# WEB_SERVER.net
KiCad netlist of a schematic drawn in Altium Designer
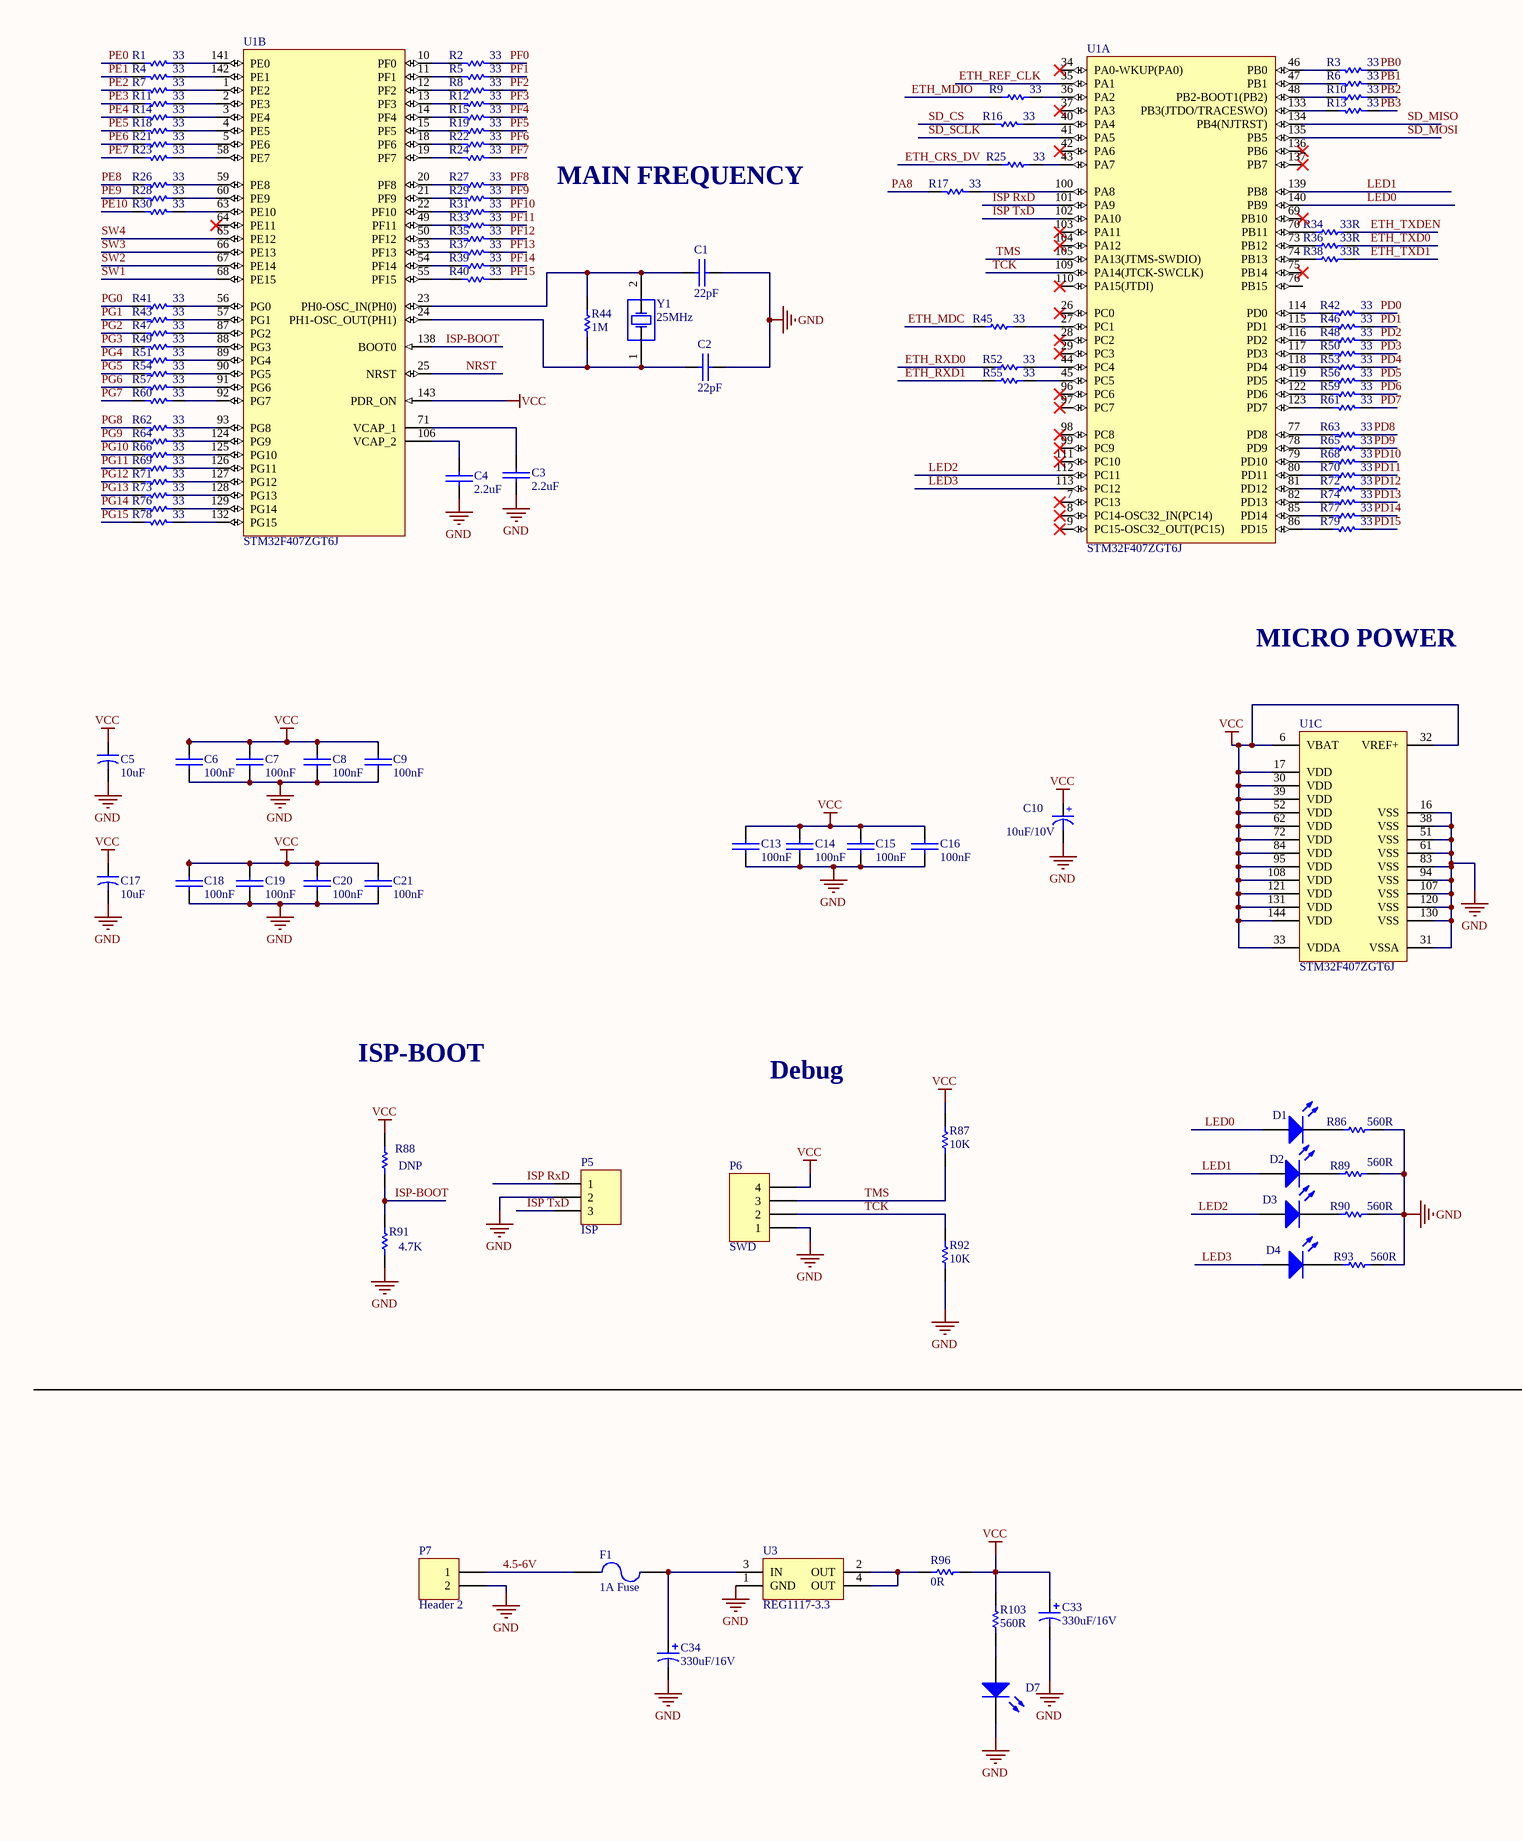
[diagram p0: WEB_SERVER.SchDoc, left]
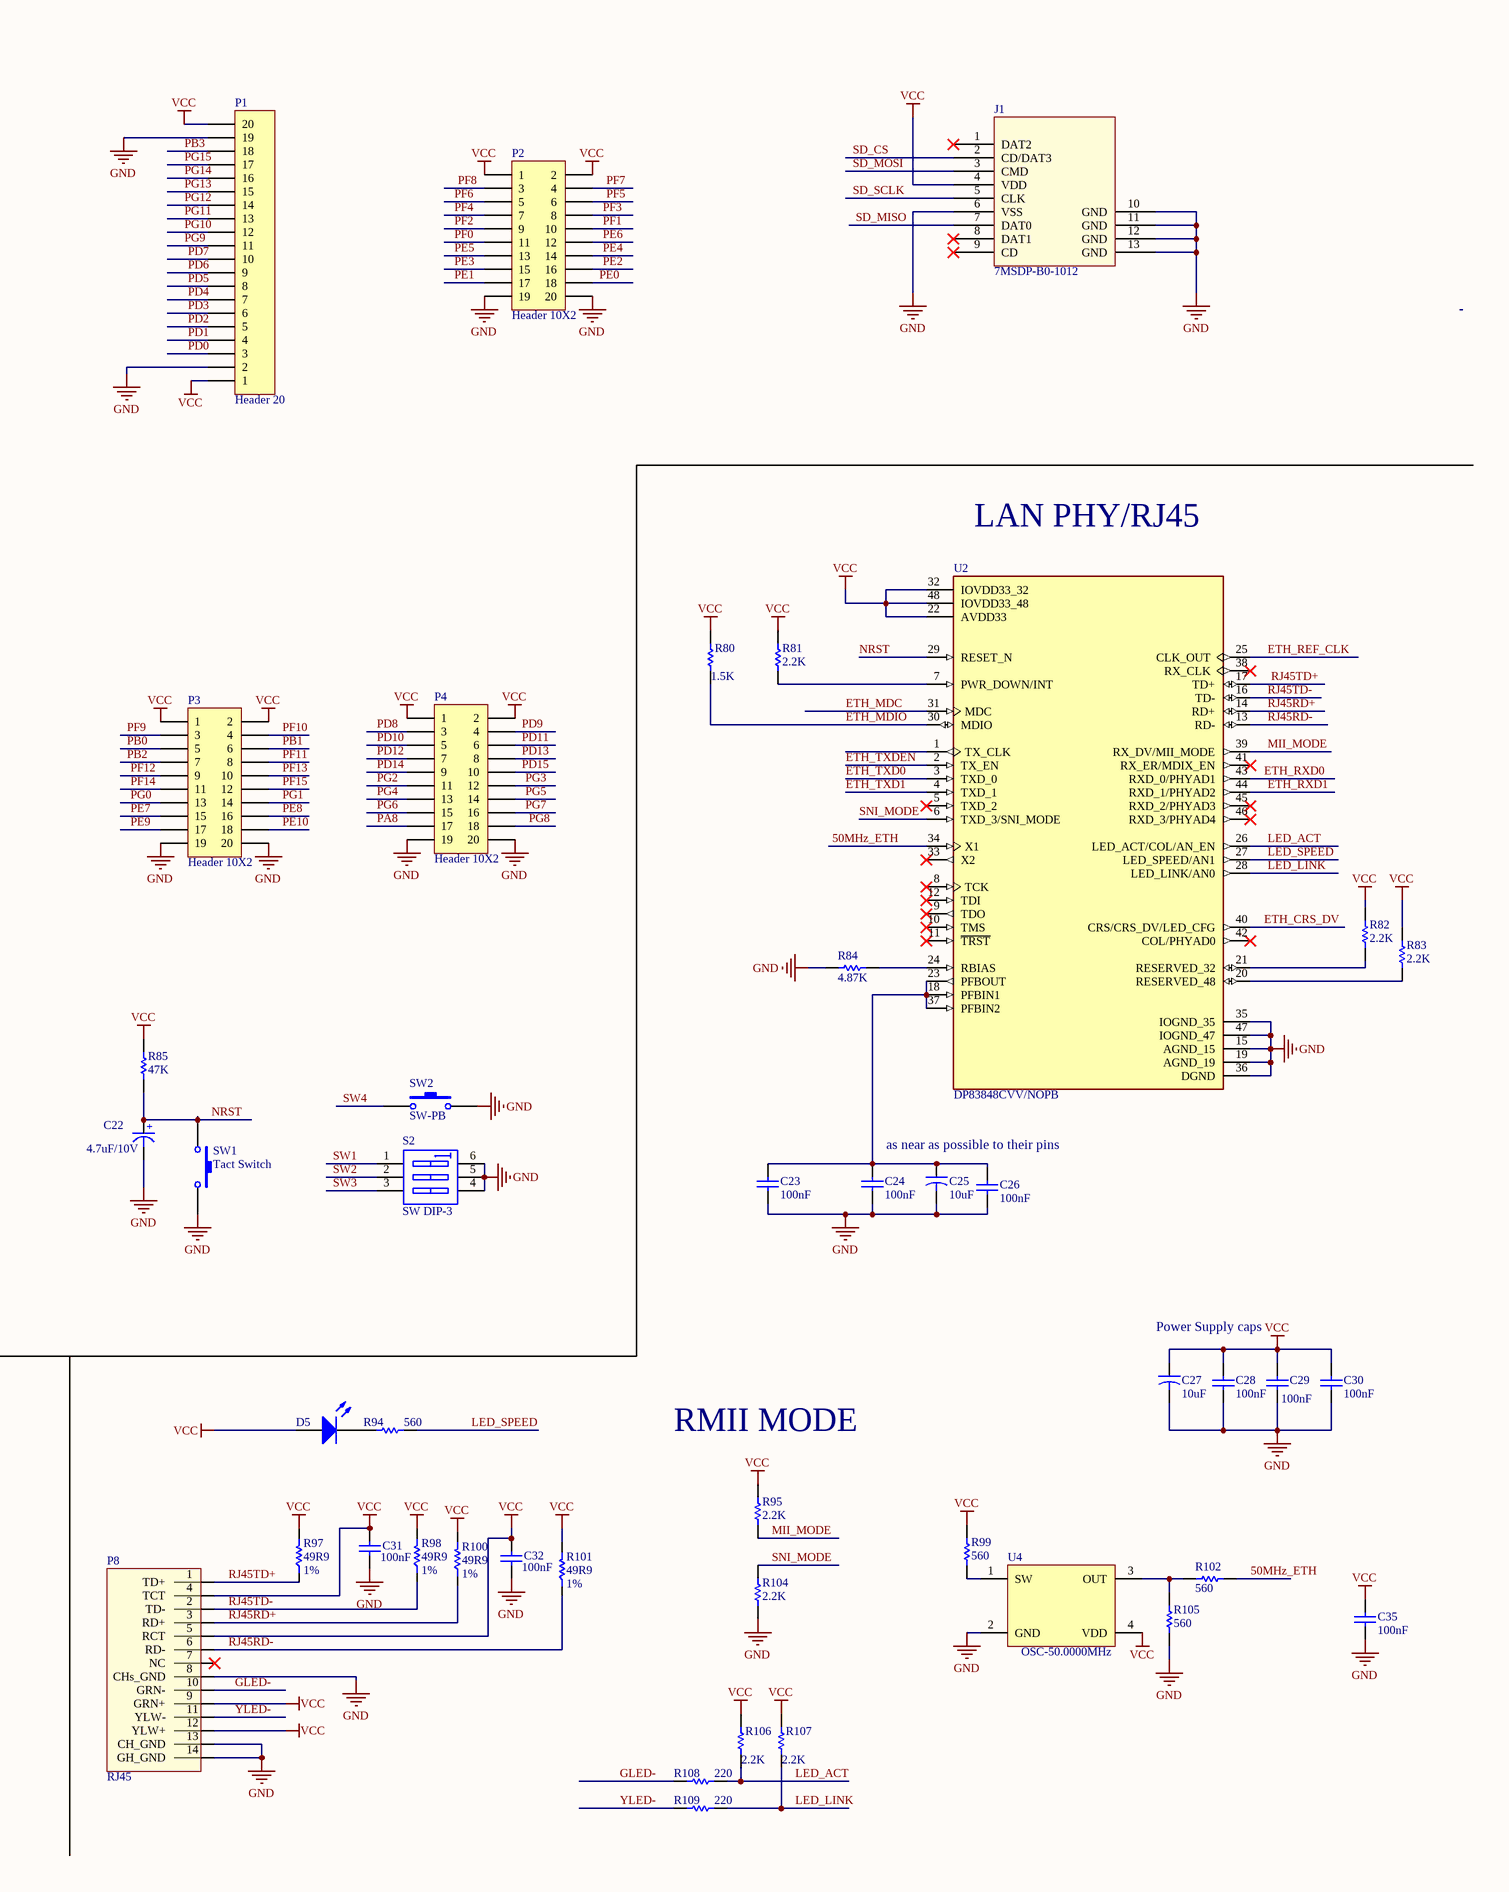
[diagram p1: WEB_SERVER.SchDoc, right]

(export (version "E")
  (design (tool "Eeschema 10.0.6"))
  (components
    (comp (ref "C1")
      (value "22pF")
      (footprint "C0805")
      (description "Bipolar Capacitor")
      (fields (field (name "VOLTAGE") "100V") (field (name "DESIGNER") "Saeid Jorablo"))
      (libsource (lib "WIZ550WEB") (part "Cap-Bipolar"))
    )
    (comp (ref "C2")
      (value "22pF")
      (footprint "C0805")
      (description "Bipolar Capacitor")
      (fields (field (name "VOLTAGE") "100V") (field (name "DESIGNER") "Saeid Jorablo"))
      (libsource (lib "WIZ550WEB") (part "Cap-Bipolar"))
    )
    (comp (ref "C3")
      (value "2.2uF")
      (footprint "C0805")
      (description "Bipolar Capacitor")
      (fields (field (name "VOLTAGE") "100V") (field (name "DESIGNER") "Saeid Jorablo"))
      (libsource (lib "WIZ550WEB") (part "Cap-Bipolar"))
    )
    (comp (ref "C4")
      (value "2.2uF")
      (footprint "C0805")
      (description "Bipolar Capacitor")
      (fields (field (name "VOLTAGE") "100V") (field (name "DESIGNER") "Saeid Jorablo"))
      (libsource (lib "WIZ550WEB") (part "Cap-Bipolar"))
    )
    (comp (ref "C5")
      (value "10uF")
      (footprint "CAP_Tantal_1206")
      (description "Capacitor Tantal")
      (fields (field (name "PUBLISHER") "Altium Limited"))
      (libsource (lib "Miscellaneous Devices") (part "Cap2"))
    )
    (comp (ref "C6")
      (value "100nF")
      (footprint "C0805")
      (description "ceramic Capacitor")
      (fields (field (name "VOLTAGE") "100V") (field (name "DESIGNER") "Saeid Jorablo"))
      (libsource (lib "WIZ550WEB") (part "Cap-Bipolar"))
    )
    (comp (ref "C7")
      (value "100nF")
      (footprint "C0805")
      (description "ceramic Capacitor")
      (fields (field (name "VOLTAGE") "100V") (field (name "DESIGNER") "Saeid Jorablo"))
      (libsource (lib "WIZ550WEB") (part "Cap-Bipolar"))
    )
    (comp (ref "C8")
      (value "100nF")
      (footprint "C0805")
      (description "ceramic Capacitor")
      (fields (field (name "VOLTAGE") "100V") (field (name "DESIGNER") "Saeid Jorablo"))
      (libsource (lib "WIZ550WEB") (part "Cap-Bipolar"))
    )
    (comp (ref "C9")
      (value "100nF")
      (footprint "C0805")
      (description "ceramic Capacitor")
      (fields (field (name "VOLTAGE") "100V") (field (name "DESIGNER") "Saeid Jorablo"))
      (libsource (lib "WIZ550WEB") (part "Cap-Bipolar"))
    )
    (comp (ref "C10")
      (value "10uF/10V")
      (footprint "CAP_Tantal_1206")
      (description "Polar Capacitor")
      (fields (field (name "VOLTAGE") "10V 3216") (field (name "DESIGNER") "Saeid Jorablo"))
      (libsource (lib "WIZ550WEB") (part "Cap-Polar"))
    )
    (comp (ref "C13")
      (value "100nF")
      (footprint "C0805")
      (description "ceramic Capacitor")
      (fields (field (name "VOLTAGE") "100V") (field (name "DESIGNER") "Saeid Jorablo"))
      (libsource (lib "WIZ550WEB") (part "Cap-Bipolar"))
    )
    (comp (ref "C14")
      (value "100nF")
      (footprint "C0805")
      (description "ceramic Capacitor")
      (fields (field (name "VOLTAGE") "100V") (field (name "DESIGNER") "Saeid Jorablo"))
      (libsource (lib "WIZ550WEB") (part "Cap-Bipolar"))
    )
    (comp (ref "C15")
      (value "100nF")
      (footprint "C0805")
      (description "ceramic Capacitor")
      (fields (field (name "VOLTAGE") "100V") (field (name "DESIGNER") "Saeid Jorablo"))
      (libsource (lib "WIZ550WEB") (part "Cap-Bipolar"))
    )
    (comp (ref "C16")
      (value "100nF")
      (footprint "C0805")
      (description "ceramic Capacitor")
      (fields (field (name "VOLTAGE") "100V") (field (name "DESIGNER") "Saeid Jorablo"))
      (libsource (lib "WIZ550WEB") (part "Cap-Bipolar"))
    )
    (comp (ref "C17")
      (value "10uF")
      (footprint "CAP_Tantal_1206")
      (description "Capacitor Tantal")
      (fields (field (name "PUBLISHER") "Altium Limited"))
      (libsource (lib "Miscellaneous Devices") (part "Cap2"))
    )
    (comp (ref "C18")
      (value "100nF")
      (footprint "C0805")
      (description "ceramic Capacitor")
      (fields (field (name "VOLTAGE") "100V") (field (name "DESIGNER") "Saeid Jorablo"))
      (libsource (lib "WIZ550WEB") (part "Cap-Bipolar"))
    )
    (comp (ref "C19")
      (value "100nF")
      (footprint "C0805")
      (description "ceramic Capacitor")
      (fields (field (name "VOLTAGE") "100V") (field (name "DESIGNER") "Saeid Jorablo"))
      (libsource (lib "WIZ550WEB") (part "Cap-Bipolar"))
    )
    (comp (ref "C20")
      (value "100nF")
      (footprint "C0805")
      (description "ceramic Capacitor")
      (fields (field (name "VOLTAGE") "100V") (field (name "DESIGNER") "Saeid Jorablo"))
      (libsource (lib "WIZ550WEB") (part "Cap-Bipolar"))
    )
    (comp (ref "C21")
      (value "100nF")
      (footprint "C0805")
      (description "ceramic Capacitor")
      (fields (field (name "VOLTAGE") "100V") (field (name "DESIGNER") "Saeid Jorablo"))
      (libsource (lib "WIZ550WEB") (part "Cap-Bipolar"))
    )
    (comp (ref "C22")
      (value "4.7uF/10V")
      (footprint "Tantalium CAPP Size A 1206 (3216X18L)")
      (description "Polar Capacitor")
      (fields (field (name "VOLTAGE") "10V 3216") (field (name "DESIGNER") "Saeid Jorablo"))
      (libsource (lib "WIZ550WEB") (part "Cap-Polar"))
    )
    (comp (ref "C23")
      (value "100nF")
      (footprint "c0805")
      (description "Capacitor")
      (fields (field (name "PUBLISHER") "Altium Limited"))
      (libsource (lib "Miscellaneous Devices") (part "Cap"))
    )
    (comp (ref "C24")
      (value "100nF")
      (footprint "c0805")
      (description "Capacitor")
      (fields (field (name "PUBLISHER") "Altium Limited"))
      (libsource (lib "Miscellaneous Devices") (part "Cap"))
    )
    (comp (ref "C25")
      (value "10uF")
      (footprint "CAP_Tantal_1206")
      (description "Capacitor Tantal")
      (fields (field (name "PUBLISHER") "Altium Limited"))
      (libsource (lib "Miscellaneous Devices") (part "Cap2"))
    )
    (comp (ref "C26")
      (value "100nF")
      (footprint "c0805")
      (description "Capacitor")
      (fields (field (name "PUBLISHER") "Altium Limited"))
      (libsource (lib "Miscellaneous Devices") (part "Cap"))
    )
    (comp (ref "C27")
      (value "10uF")
      (footprint "CAP_Tantal_1206")
      (description "Capacitor Tantal")
      (fields (field (name "PUBLISHER") "Altium Limited"))
      (libsource (lib "Miscellaneous Devices") (part "Cap2"))
    )
    (comp (ref "C28")
      (value "100nF")
      (footprint "c0805")
      (description "Capacitor")
      (fields (field (name "PUBLISHER") "Altium Limited"))
      (libsource (lib "Miscellaneous Devices") (part "Cap"))
    )
    (comp (ref "C29")
      (value "100nF")
      (footprint "c0805")
      (description "Capacitor")
      (fields (field (name "PUBLISHER") "Altium Limited"))
      (libsource (lib "Miscellaneous Devices") (part "Cap"))
    )
    (comp (ref "C30")
      (value "100nF")
      (footprint "c0805")
      (description "Capacitor")
      (fields (field (name "PUBLISHER") "Altium Limited"))
      (libsource (lib "Miscellaneous Devices") (part "Cap"))
    )
    (comp (ref "C31")
      (value "100nF")
      (footprint "c0805")
      (description "Capacitor")
      (fields (field (name "PUBLISHER") "Altium Limited"))
      (libsource (lib "Miscellaneous Devices") (part "Cap"))
    )
    (comp (ref "C32")
      (value "100nF")
      (footprint "c0805")
      (description "Capacitor")
      (fields (field (name "PUBLISHER") "Altium Limited"))
      (libsource (lib "Miscellaneous Devices") (part "Cap"))
    )
    (comp (ref "C33")
      (value "330uF/16V")
      (footprint "RB.15/.3")
      (description "Polarized Capacitor (Radial)")
      (fields (field (name "PUBLISHER") "Altium Limited"))
      (libsource (lib "Miscellaneous Devices") (part "Cap Pol1"))
    )
    (comp (ref "C34")
      (value "330uF/16V")
      (footprint "RB.15/.3")
      (description "Polarized Capacitor (Radial)")
      (fields (field (name "PUBLISHER") "Altium Limited"))
      (libsource (lib "Miscellaneous Devices") (part "Cap Pol1"))
    )
    (comp (ref "C35")
      (value "100nF")
      (footprint "c0805")
      (description "Capacitor")
      (fields (field (name "PUBLISHER") "Altium Limited"))
      (libsource (lib "Miscellaneous Devices") (part "Cap"))
    )
    (comp (ref "D1")
      (value "LED1")
      (footprint "LED_805")
      (description "Typical BLUE SiC LED")
      (fields (field (name "PUBLISHER") "Altium Limited"))
      (libsource (lib "Miscellaneous Devices") (part "LED3"))
    )
    (comp (ref "D2")
      (value "LED1")
      (footprint "LED_805")
      (description "Typical BLUE SiC LED")
      (fields (field (name "PUBLISHER") "Altium Limited"))
      (libsource (lib "Miscellaneous Devices") (part "LED3"))
    )
    (comp (ref "D3")
      (value "LED2")
      (footprint "LED_805")
      (description "Typical BLUE SiC LED")
      (fields (field (name "PUBLISHER") "Altium Limited"))
      (libsource (lib "Miscellaneous Devices") (part "LED3"))
    )
    (comp (ref "D4")
      (value "LED3")
      (footprint "LED_805")
      (description "Typical BLUE SiC LED")
      (fields (field (name "PUBLISHER") "Altium Limited"))
      (libsource (lib "Miscellaneous Devices") (part "LED3"))
    )
    (comp (ref "D5")
      (value "SPEED(G)")
      (footprint "LED0805")
      (description "Typical BLUE SiC LED")
      (fields (field (name "PUBLISHER") "Altium Limited"))
      (libsource (lib "Miscellaneous Devices") (part "LED3"))
    )
    (comp (ref "D7")
      (value "LED G")
      (footprint "LED_805")
      (description "Typical BLUE SiC LED")
      (fields (field (name "PUBLISHER") "Altium Limited"))
      (libsource (lib "Miscellaneous Devices") (part "LED3"))
    )
    (comp (ref "F1")
      (value "1A Fuse")
      (footprint "6-0805_L")
      (description "Fuse")
      (fields (field (name "PUBLISHER") "Altium Limited"))
      (libsource (lib "Miscellaneous Devices") (part "Fuse 2"))
    )
    (comp (ref "J1")
      (value "7MSDP-B0-1012")
      (footprint "MicroSD Slot")
      (description "MicroSD Slot")
      (libsource (lib "WIZ550WEB") (part "7MSDP-B0-1012"))
    )
    (comp (ref "P1")
      (value "Header 20")
      (footprint "HDR1X20")
      (description "Header, 20-Pin")
      (fields (field (name "PUBLISHER") "Altium Limited"))
      (libsource (lib "Miscellaneous Connectors") (part "Header 20"))
    )
    (comp (ref "P2")
      (value "Header 10X2")
      (footprint "HDR2X10")
      (description "Header, 10-Pin, Dual row")
      (fields (field (name "PUBLISHER") "Altium Limited"))
      (libsource (lib "Miscellaneous Connectors") (part "Header 10X2"))
    )
    (comp (ref "P3")
      (value "Header 10X2")
      (footprint "HDR2X10")
      (description "Header, 10-Pin, Dual row")
      (fields (field (name "PUBLISHER") "Altium Limited"))
      (libsource (lib "Miscellaneous Connectors") (part "Header 10X2"))
    )
    (comp (ref "P4")
      (value "Header 10X2")
      (footprint "HDR2X10")
      (description "Header, 10-Pin, Dual row")
      (fields (field (name "PUBLISHER") "Altium Limited"))
      (libsource (lib "Miscellaneous Connectors") (part "Header 10X2"))
    )
    (comp (ref "P5")
      (value "ISP")
      (footprint "HDR1X3")
      (description "Header, 3-Pin")
      (fields (field (name "PUBLISHER") "Altium Limited"))
      (libsource (lib "Miscellaneous Connectors") (part "Header 3"))
    )
    (comp (ref "P6")
      (value "SWD")
      (footprint "HDR1X4")
      (description "Header, 4-Pin")
      (fields (field (name "PUBLISHER") "Altium Limited"))
      (libsource (lib "Miscellaneous Connectors") (part "Header 4"))
    )
    (comp (ref "P7")
      (value "Header 2")
      (footprint "HDR1X2")
      (description "Header, 2-Pin")
      (fields (field (name "PUBLISHER") "Altium Limited"))
      (libsource (lib "Miscellaneous Connectors") (part "Header 2"))
    )
    (comp (ref "P8") (value "RJ45") (footprint "RJ245") (libsource (lib "WIZ550WEB") (part "RJ245")))
    (comp (ref "R1")
      (value "33")
      (footprint "6-0805_L")
      (description "Semiconductor Resistor")
      (fields (field (name "PUBLISHER") "Altium Limited"))
      (libsource (lib "Miscellaneous Devices") (part "Res Semi"))
    )
    (comp (ref "R2")
      (value "33")
      (footprint "6-0805_L")
      (description "Semiconductor Resistor")
      (fields (field (name "PUBLISHER") "Altium Limited"))
      (libsource (lib "Miscellaneous Devices") (part "Res Semi"))
    )
    (comp (ref "R3")
      (value "33")
      (footprint "6-0805_L")
      (description "Semiconductor Resistor")
      (fields (field (name "PUBLISHER") "Altium Limited"))
      (libsource (lib "Miscellaneous Devices") (part "Res Semi"))
    )
    (comp (ref "R4")
      (value "33")
      (footprint "6-0805_L")
      (description "Semiconductor Resistor")
      (fields (field (name "PUBLISHER") "Altium Limited"))
      (libsource (lib "Miscellaneous Devices") (part "Res Semi"))
    )
    (comp (ref "R5")
      (value "33")
      (footprint "6-0805_L")
      (description "Semiconductor Resistor")
      (fields (field (name "PUBLISHER") "Altium Limited"))
      (libsource (lib "Miscellaneous Devices") (part "Res Semi"))
    )
    (comp (ref "R6")
      (value "33")
      (footprint "6-0805_L")
      (description "Semiconductor Resistor")
      (fields (field (name "PUBLISHER") "Altium Limited"))
      (libsource (lib "Miscellaneous Devices") (part "Res Semi"))
    )
    (comp (ref "R7")
      (value "33")
      (footprint "6-0805_L")
      (description "Semiconductor Resistor")
      (fields (field (name "PUBLISHER") "Altium Limited"))
      (libsource (lib "Miscellaneous Devices") (part "Res Semi"))
    )
    (comp (ref "R8")
      (value "33")
      (footprint "6-0805_L")
      (description "Semiconductor Resistor")
      (fields (field (name "PUBLISHER") "Altium Limited"))
      (libsource (lib "Miscellaneous Devices") (part "Res Semi"))
    )
    (comp (ref "R9")
      (value "33")
      (footprint "c0805")
      (description "Resistor")
      (fields (field (name "PUBLISHER") "Altium Limited"))
      (libsource (lib "Miscellaneous Devices") (part "Res1"))
    )
    (comp (ref "R10")
      (value "33")
      (footprint "6-0805_L")
      (description "Semiconductor Resistor")
      (fields (field (name "PUBLISHER") "Altium Limited"))
      (libsource (lib "Miscellaneous Devices") (part "Res Semi"))
    )
    (comp (ref "R11")
      (value "33")
      (footprint "6-0805_L")
      (description "Semiconductor Resistor")
      (fields (field (name "PUBLISHER") "Altium Limited"))
      (libsource (lib "Miscellaneous Devices") (part "Res Semi"))
    )
    (comp (ref "R12")
      (value "33")
      (footprint "6-0805_L")
      (description "Semiconductor Resistor")
      (fields (field (name "PUBLISHER") "Altium Limited"))
      (libsource (lib "Miscellaneous Devices") (part "Res Semi"))
    )
    (comp (ref "R13")
      (value "33")
      (footprint "6-0805_L")
      (description "Semiconductor Resistor")
      (fields (field (name "PUBLISHER") "Altium Limited"))
      (libsource (lib "Miscellaneous Devices") (part "Res Semi"))
    )
    (comp (ref "R14")
      (value "33")
      (footprint "6-0805_L")
      (description "Semiconductor Resistor")
      (fields (field (name "PUBLISHER") "Altium Limited"))
      (libsource (lib "Miscellaneous Devices") (part "Res Semi"))
    )
    (comp (ref "R15")
      (value "33")
      (footprint "6-0805_L")
      (description "Semiconductor Resistor")
      (fields (field (name "PUBLISHER") "Altium Limited"))
      (libsource (lib "Miscellaneous Devices") (part "Res Semi"))
    )
    (comp (ref "R16")
      (value "33")
      (footprint "6-0805_L")
      (description "Semiconductor Resistor")
      (fields (field (name "PUBLISHER") "Altium Limited"))
      (libsource (lib "Miscellaneous Devices") (part "Res Semi"))
    )
    (comp (ref "R17")
      (value "33")
      (footprint "6-0805_L")
      (description "Semiconductor Resistor")
      (fields (field (name "PUBLISHER") "Altium Limited"))
      (libsource (lib "Miscellaneous Devices") (part "Res Semi"))
    )
    (comp (ref "R18")
      (value "33")
      (footprint "6-0805_L")
      (description "Semiconductor Resistor")
      (fields (field (name "PUBLISHER") "Altium Limited"))
      (libsource (lib "Miscellaneous Devices") (part "Res Semi"))
    )
    (comp (ref "R19")
      (value "33")
      (footprint "6-0805_L")
      (description "Semiconductor Resistor")
      (fields (field (name "PUBLISHER") "Altium Limited"))
      (libsource (lib "Miscellaneous Devices") (part "Res Semi"))
    )
    (comp (ref "R21")
      (value "33")
      (footprint "6-0805_L")
      (description "Semiconductor Resistor")
      (fields (field (name "PUBLISHER") "Altium Limited"))
      (libsource (lib "Miscellaneous Devices") (part "Res Semi"))
    )
    (comp (ref "R22")
      (value "33")
      (footprint "6-0805_L")
      (description "Semiconductor Resistor")
      (fields (field (name "PUBLISHER") "Altium Limited"))
      (libsource (lib "Miscellaneous Devices") (part "Res Semi"))
    )
    (comp (ref "R23")
      (value "33")
      (footprint "6-0805_L")
      (description "Semiconductor Resistor")
      (fields (field (name "PUBLISHER") "Altium Limited"))
      (libsource (lib "Miscellaneous Devices") (part "Res Semi"))
    )
    (comp (ref "R24")
      (value "33")
      (footprint "6-0805_L")
      (description "Semiconductor Resistor")
      (fields (field (name "PUBLISHER") "Altium Limited"))
      (libsource (lib "Miscellaneous Devices") (part "Res Semi"))
    )
    (comp (ref "R25")
      (value "33")
      (footprint "c0805")
      (description "Resistor")
      (fields (field (name "PUBLISHER") "Altium Limited"))
      (libsource (lib "Miscellaneous Devices") (part "Res1"))
    )
    (comp (ref "R26")
      (value "33")
      (footprint "6-0805_L")
      (description "Semiconductor Resistor")
      (fields (field (name "PUBLISHER") "Altium Limited"))
      (libsource (lib "Miscellaneous Devices") (part "Res Semi"))
    )
    (comp (ref "R27")
      (value "33")
      (footprint "6-0805_L")
      (description "Semiconductor Resistor")
      (fields (field (name "PUBLISHER") "Altium Limited"))
      (libsource (lib "Miscellaneous Devices") (part "Res Semi"))
    )
    (comp (ref "R28")
      (value "33")
      (footprint "6-0805_L")
      (description "Semiconductor Resistor")
      (fields (field (name "PUBLISHER") "Altium Limited"))
      (libsource (lib "Miscellaneous Devices") (part "Res Semi"))
    )
    (comp (ref "R29")
      (value "33")
      (footprint "6-0805_L")
      (description "Semiconductor Resistor")
      (fields (field (name "PUBLISHER") "Altium Limited"))
      (libsource (lib "Miscellaneous Devices") (part "Res Semi"))
    )
    (comp (ref "R30")
      (value "33")
      (footprint "6-0805_L")
      (description "Semiconductor Resistor")
      (fields (field (name "PUBLISHER") "Altium Limited"))
      (libsource (lib "Miscellaneous Devices") (part "Res Semi"))
    )
    (comp (ref "R31")
      (value "33")
      (footprint "6-0805_L")
      (description "Semiconductor Resistor")
      (fields (field (name "PUBLISHER") "Altium Limited"))
      (libsource (lib "Miscellaneous Devices") (part "Res Semi"))
    )
    (comp (ref "R33")
      (value "33")
      (footprint "6-0805_L")
      (description "Semiconductor Resistor")
      (fields (field (name "PUBLISHER") "Altium Limited"))
      (libsource (lib "Miscellaneous Devices") (part "Res Semi"))
    )
    (comp (ref "R34")
      (value "33R")
      (footprint "6-0805_L")
      (description "Semiconductor Resistor")
      (fields (field (name "PUBLISHER") "Altium Limited"))
      (libsource (lib "Miscellaneous Devices") (part "Res Semi"))
    )
    (comp (ref "R35")
      (value "33")
      (footprint "6-0805_L")
      (description "Semiconductor Resistor")
      (fields (field (name "PUBLISHER") "Altium Limited"))
      (libsource (lib "Miscellaneous Devices") (part "Res Semi"))
    )
    (comp (ref "R36")
      (value "33R")
      (footprint "6-0805_L")
      (description "Semiconductor Resistor")
      (fields (field (name "PUBLISHER") "Altium Limited"))
      (libsource (lib "Miscellaneous Devices") (part "Res Semi"))
    )
    (comp (ref "R37")
      (value "33")
      (footprint "6-0805_L")
      (description "Semiconductor Resistor")
      (fields (field (name "PUBLISHER") "Altium Limited"))
      (libsource (lib "Miscellaneous Devices") (part "Res Semi"))
    )
    (comp (ref "R38")
      (value "33R")
      (footprint "6-0805_L")
      (description "Semiconductor Resistor")
      (fields (field (name "PUBLISHER") "Altium Limited"))
      (libsource (lib "Miscellaneous Devices") (part "Res Semi"))
    )
    (comp (ref "R39")
      (value "33")
      (footprint "6-0805_L")
      (description "Semiconductor Resistor")
      (fields (field (name "PUBLISHER") "Altium Limited"))
      (libsource (lib "Miscellaneous Devices") (part "Res Semi"))
    )
    (comp (ref "R40")
      (value "33")
      (footprint "6-0805_L")
      (description "Semiconductor Resistor")
      (fields (field (name "PUBLISHER") "Altium Limited"))
      (libsource (lib "Miscellaneous Devices") (part "Res Semi"))
    )
    (comp (ref "R41")
      (value "33")
      (footprint "6-0805_L")
      (description "Semiconductor Resistor")
      (fields (field (name "PUBLISHER") "Altium Limited"))
      (libsource (lib "Miscellaneous Devices") (part "Res Semi"))
    )
    (comp (ref "R42")
      (value "33")
      (footprint "6-0805_L")
      (description "Semiconductor Resistor")
      (fields (field (name "PUBLISHER") "Altium Limited"))
      (libsource (lib "Miscellaneous Devices") (part "Res Semi"))
    )
    (comp (ref "R43")
      (value "33")
      (footprint "6-0805_L")
      (description "Semiconductor Resistor")
      (fields (field (name "PUBLISHER") "Altium Limited"))
      (libsource (lib "Miscellaneous Devices") (part "Res Semi"))
    )
    (comp (ref "R44")
      (value "1M")
      (footprint "c0805")
      (description "Resistor")
      (fields (field (name "PUBLISHER") "Altium Limited"))
      (libsource (lib "Miscellaneous Devices") (part "Res1"))
    )
    (comp (ref "R45")
      (value "33")
      (footprint "c0805")
      (description "Resistor")
      (fields (field (name "PUBLISHER") "Altium Limited"))
      (libsource (lib "Miscellaneous Devices") (part "Res1"))
    )
    (comp (ref "R46")
      (value "33")
      (footprint "6-0805_L")
      (description "Semiconductor Resistor")
      (fields (field (name "PUBLISHER") "Altium Limited"))
      (libsource (lib "Miscellaneous Devices") (part "Res Semi"))
    )
    (comp (ref "R47")
      (value "33")
      (footprint "6-0805_L")
      (description "Semiconductor Resistor")
      (fields (field (name "PUBLISHER") "Altium Limited"))
      (libsource (lib "Miscellaneous Devices") (part "Res Semi"))
    )
    (comp (ref "R48")
      (value "33")
      (footprint "6-0805_L")
      (description "Semiconductor Resistor")
      (fields (field (name "PUBLISHER") "Altium Limited"))
      (libsource (lib "Miscellaneous Devices") (part "Res Semi"))
    )
    (comp (ref "R49")
      (value "33")
      (footprint "6-0805_L")
      (description "Semiconductor Resistor")
      (fields (field (name "PUBLISHER") "Altium Limited"))
      (libsource (lib "Miscellaneous Devices") (part "Res Semi"))
    )
    (comp (ref "R50")
      (value "33")
      (footprint "6-0805_L")
      (description "Semiconductor Resistor")
      (fields (field (name "PUBLISHER") "Altium Limited"))
      (libsource (lib "Miscellaneous Devices") (part "Res Semi"))
    )
    (comp (ref "R51")
      (value "33")
      (footprint "6-0805_L")
      (description "Semiconductor Resistor")
      (fields (field (name "PUBLISHER") "Altium Limited"))
      (libsource (lib "Miscellaneous Devices") (part "Res Semi"))
    )
    (comp (ref "R52")
      (value "33")
      (footprint "c0805")
      (description "Resistor")
      (fields (field (name "PUBLISHER") "Altium Limited"))
      (libsource (lib "Miscellaneous Devices") (part "Res1"))
    )
    (comp (ref "R53")
      (value "33")
      (footprint "6-0805_L")
      (description "Semiconductor Resistor")
      (fields (field (name "PUBLISHER") "Altium Limited"))
      (libsource (lib "Miscellaneous Devices") (part "Res Semi"))
    )
    (comp (ref "R54")
      (value "33")
      (footprint "6-0805_L")
      (description "Semiconductor Resistor")
      (fields (field (name "PUBLISHER") "Altium Limited"))
      (libsource (lib "Miscellaneous Devices") (part "Res Semi"))
    )
    (comp (ref "R55")
      (value "33")
      (footprint "c0805")
      (description "Resistor")
      (fields (field (name "PUBLISHER") "Altium Limited"))
      (libsource (lib "Miscellaneous Devices") (part "Res1"))
    )
    (comp (ref "R56")
      (value "33")
      (footprint "6-0805_L")
      (description "Semiconductor Resistor")
      (fields (field (name "PUBLISHER") "Altium Limited"))
      (libsource (lib "Miscellaneous Devices") (part "Res Semi"))
    )
    (comp (ref "R57")
      (value "33")
      (footprint "6-0805_L")
      (description "Semiconductor Resistor")
      (fields (field (name "PUBLISHER") "Altium Limited"))
      (libsource (lib "Miscellaneous Devices") (part "Res Semi"))
    )
    (comp (ref "R59")
      (value "33")
      (footprint "6-0805_L")
      (description "Semiconductor Resistor")
      (fields (field (name "PUBLISHER") "Altium Limited"))
      (libsource (lib "Miscellaneous Devices") (part "Res Semi"))
    )
    (comp (ref "R60")
      (value "33")
      (footprint "6-0805_L")
      (description "Semiconductor Resistor")
      (fields (field (name "PUBLISHER") "Altium Limited"))
      (libsource (lib "Miscellaneous Devices") (part "Res Semi"))
    )
    (comp (ref "R61")
      (value "33")
      (footprint "6-0805_L")
      (description "Semiconductor Resistor")
      (fields (field (name "PUBLISHER") "Altium Limited"))
      (libsource (lib "Miscellaneous Devices") (part "Res Semi"))
    )
    (comp (ref "R62")
      (value "33")
      (footprint "6-0805_L")
      (description "Semiconductor Resistor")
      (fields (field (name "PUBLISHER") "Altium Limited"))
      (libsource (lib "Miscellaneous Devices") (part "Res Semi"))
    )
    (comp (ref "R63")
      (value "33")
      (footprint "6-0805_L")
      (description "Semiconductor Resistor")
      (fields (field (name "PUBLISHER") "Altium Limited"))
      (libsource (lib "Miscellaneous Devices") (part "Res Semi"))
    )
    (comp (ref "R64")
      (value "33")
      (footprint "6-0805_L")
      (description "Semiconductor Resistor")
      (fields (field (name "PUBLISHER") "Altium Limited"))
      (libsource (lib "Miscellaneous Devices") (part "Res Semi"))
    )
    (comp (ref "R65")
      (value "33")
      (footprint "6-0805_L")
      (description "Semiconductor Resistor")
      (fields (field (name "PUBLISHER") "Altium Limited"))
      (libsource (lib "Miscellaneous Devices") (part "Res Semi"))
    )
    (comp (ref "R66")
      (value "33")
      (footprint "6-0805_L")
      (description "Semiconductor Resistor")
      (fields (field (name "PUBLISHER") "Altium Limited"))
      (libsource (lib "Miscellaneous Devices") (part "Res Semi"))
    )
    (comp (ref "R68")
      (value "33")
      (footprint "6-0805_L")
      (description "Semiconductor Resistor")
      (fields (field (name "PUBLISHER") "Altium Limited"))
      (libsource (lib "Miscellaneous Devices") (part "Res Semi"))
    )
    (comp (ref "R69")
      (value "33")
      (footprint "6-0805_L")
      (description "Semiconductor Resistor")
      (fields (field (name "PUBLISHER") "Altium Limited"))
      (libsource (lib "Miscellaneous Devices") (part "Res Semi"))
    )
    (comp (ref "R70")
      (value "33")
      (footprint "6-0805_L")
      (description "Semiconductor Resistor")
      (fields (field (name "PUBLISHER") "Altium Limited"))
      (libsource (lib "Miscellaneous Devices") (part "Res Semi"))
    )
    (comp (ref "R71")
      (value "33")
      (footprint "6-0805_L")
      (description "Semiconductor Resistor")
      (fields (field (name "PUBLISHER") "Altium Limited"))
      (libsource (lib "Miscellaneous Devices") (part "Res Semi"))
    )
    (comp (ref "R72")
      (value "33")
      (footprint "6-0805_L")
      (description "Semiconductor Resistor")
      (fields (field (name "PUBLISHER") "Altium Limited"))
      (libsource (lib "Miscellaneous Devices") (part "Res Semi"))
    )
    (comp (ref "R73")
      (value "33")
      (footprint "6-0805_L")
      (description "Semiconductor Resistor")
      (fields (field (name "PUBLISHER") "Altium Limited"))
      (libsource (lib "Miscellaneous Devices") (part "Res Semi"))
    )
    (comp (ref "R74")
      (value "33")
      (footprint "6-0805_L")
      (description "Semiconductor Resistor")
      (fields (field (name "PUBLISHER") "Altium Limited"))
      (libsource (lib "Miscellaneous Devices") (part "Res Semi"))
    )
    (comp (ref "R76")
      (value "33")
      (footprint "6-0805_L")
      (description "Semiconductor Resistor")
      (fields (field (name "PUBLISHER") "Altium Limited"))
      (libsource (lib "Miscellaneous Devices") (part "Res Semi"))
    )
    (comp (ref "R77")
      (value "33")
      (footprint "6-0805_L")
      (description "Semiconductor Resistor")
      (fields (field (name "PUBLISHER") "Altium Limited"))
      (libsource (lib "Miscellaneous Devices") (part "Res Semi"))
    )
    (comp (ref "R78")
      (value "33")
      (footprint "6-0805_L")
      (description "Semiconductor Resistor")
      (fields (field (name "PUBLISHER") "Altium Limited"))
      (libsource (lib "Miscellaneous Devices") (part "Res Semi"))
    )
    (comp (ref "R79")
      (value "33")
      (footprint "6-0805_L")
      (description "Semiconductor Resistor")
      (fields (field (name "PUBLISHER") "Altium Limited"))
      (libsource (lib "Miscellaneous Devices") (part "Res Semi"))
    )
    (comp (ref "R80")
      (value "1.5K")
      (footprint "c0805")
      (description "Resistor")
      (fields (field (name "PUBLISHER") "Altium Limited"))
      (libsource (lib "Miscellaneous Devices") (part "Res1"))
    )
    (comp (ref "R81")
      (value "2.2K")
      (footprint "c0805")
      (description "Semiconductor Resistor")
      (fields (field (name "PUBLISHER") "Altium Limited"))
      (libsource (lib "Miscellaneous Devices") (part "Res Semi"))
    )
    (comp (ref "R82")
      (value "2.2K")
      (footprint "c0805")
      (description "Semiconductor Resistor")
      (fields (field (name "PUBLISHER") "Altium Limited"))
      (libsource (lib "Miscellaneous Devices") (part "Res Semi"))
    )
    (comp (ref "R83")
      (value "2.2K")
      (footprint "c0805")
      (description "Semiconductor Resistor")
      (fields (field (name "PUBLISHER") "Altium Limited"))
      (libsource (lib "Miscellaneous Devices") (part "Res Semi"))
    )
    (comp (ref "R84")
      (value "4.87K")
      (footprint "c0805")
      (description "Resistor 1%")
      (fields (field (name "PUBLISHER") "Altium Limited"))
      (libsource (lib "Miscellaneous Devices") (part "Res1"))
    )
    (comp (ref "R85")
      (value "47K")
      (footprint "6-0805_L")
      (description "Semiconductor Resistor")
      (fields (field (name "PUBLISHER") "Altium Limited"))
      (libsource (lib "Miscellaneous Devices") (part "Res Semi"))
    )
    (comp (ref "R86")
      (value "560R")
      (footprint "6-0805_L")
      (description "Semiconductor Resistor")
      (fields (field (name "PUBLISHER") "Altium Limited"))
      (libsource (lib "Miscellaneous Devices") (part "Res Semi"))
    )
    (comp (ref "R87")
      (value "10K")
      (footprint "6-0805_L")
      (description "Semiconductor Resistor")
      (fields (field (name "PUBLISHER") "Altium Limited"))
      (libsource (lib "Miscellaneous Devices") (part "Res Semi"))
    )
    (comp (ref "R88")
      (value "DNP")
      (footprint "6-0805_L")
      (description "Semiconductor Resistor")
      (fields (field (name "PUBLISHER") "Altium Limited"))
      (libsource (lib "Miscellaneous Devices") (part "Res Semi"))
    )
    (comp (ref "R89")
      (value "560R")
      (footprint "6-0805_L")
      (description "Semiconductor Resistor")
      (fields (field (name "PUBLISHER") "Altium Limited"))
      (libsource (lib "Miscellaneous Devices") (part "Res Semi"))
    )
    (comp (ref "R90")
      (value "560R")
      (footprint "6-0805_L")
      (description "Semiconductor Resistor")
      (fields (field (name "PUBLISHER") "Altium Limited"))
      (libsource (lib "Miscellaneous Devices") (part "Res Semi"))
    )
    (comp (ref "R91")
      (value "4.7K")
      (footprint "6-0805_L")
      (description "Semiconductor Resistor")
      (fields (field (name "PUBLISHER") "Altium Limited"))
      (libsource (lib "Miscellaneous Devices") (part "Res Semi"))
    )
    (comp (ref "R92")
      (value "10K")
      (footprint "6-0805_L")
      (description "Semiconductor Resistor")
      (fields (field (name "PUBLISHER") "Altium Limited"))
      (libsource (lib "Miscellaneous Devices") (part "Res Semi"))
    )
    (comp (ref "R93")
      (value "560R")
      (footprint "6-0805_L")
      (description "Semiconductor Resistor")
      (fields (field (name "PUBLISHER") "Altium Limited"))
      (libsource (lib "Miscellaneous Devices") (part "Res Semi"))
    )
    (comp (ref "R94")
      (value "560")
      (footprint "c0805")
      (description "Semiconductor Resistor")
      (fields (field (name "PUBLISHER") "Altium Limited"))
      (libsource (lib "Miscellaneous Devices") (part "Res Semi"))
    )
    (comp (ref "R95")
      (value "2.2K")
      (footprint "c0805")
      (description "Semiconductor Resistor")
      (fields (field (name "PUBLISHER") "Altium Limited"))
      (libsource (lib "Miscellaneous Devices") (part "Res Semi"))
    )
    (comp (ref "R96")
      (value "0R")
      (footprint "6-0805_L")
      (description "Semiconductor Resistor")
      (fields (field (name "PUBLISHER") "Altium Limited"))
      (libsource (lib "Miscellaneous Devices") (part "Res Semi"))
    )
    (comp (ref "R97")
      (value "49R9")
      (footprint "c0805")
      (description "Resistor")
      (fields (field (name "TOLERANCE") "1%") (field (name "POWER") "1/8 W"))
      (libsource (lib "WIZ550WEB") (part "Resistor"))
    )
    (comp (ref "R98")
      (value "49R9")
      (footprint "c0805")
      (description "Resistor")
      (fields (field (name "TOLERANCE") "1%") (field (name "POWER") "1/8 W"))
      (libsource (lib "WIZ550WEB") (part "Resistor"))
    )
    (comp (ref "R99")
      (value "560")
      (footprint "c0805")
      (description "Semiconductor Resistor")
      (fields (field (name "PUBLISHER") "Altium Limited"))
      (libsource (lib "Miscellaneous Devices") (part "Res Semi"))
    )
    (comp (ref "R100")
      (value "49R9")
      (footprint "c0805")
      (description "Resistor")
      (fields (field (name "TOLERANCE") "1%") (field (name "POWER") "1/8 W"))
      (libsource (lib "WIZ550WEB") (part "Resistor"))
    )
    (comp (ref "R101")
      (value "49R9")
      (footprint "c0805")
      (description "Resistor")
      (fields (field (name "TOLERANCE") "1%") (field (name "POWER") "1/8 W"))
      (libsource (lib "WIZ550WEB") (part "Resistor"))
    )
    (comp (ref "R102")
      (value "560")
      (footprint "c0805")
      (description "Semiconductor Resistor")
      (fields (field (name "PUBLISHER") "Altium Limited"))
      (libsource (lib "Miscellaneous Devices") (part "Res Semi"))
    )
    (comp (ref "R103")
      (value "560R")
      (footprint "6-0805_L")
      (description "Semiconductor Resistor")
      (fields (field (name "PUBLISHER") "Altium Limited"))
      (libsource (lib "Miscellaneous Devices") (part "Res Semi"))
    )
    (comp (ref "R104")
      (value "2.2K")
      (footprint "c0805")
      (description "Semiconductor Resistor")
      (fields (field (name "PUBLISHER") "Altium Limited"))
      (libsource (lib "Miscellaneous Devices") (part "Res Semi"))
    )
    (comp (ref "R105")
      (value "560")
      (footprint "c0805")
      (description "Semiconductor Resistor")
      (fields (field (name "PUBLISHER") "Altium Limited"))
      (libsource (lib "Miscellaneous Devices") (part "Res Semi"))
    )
    (comp (ref "R106")
      (value "2.2K")
      (footprint "c0805")
      (description "Resistor")
      (fields (field (name "PUBLISHER") "Altium Limited"))
      (libsource (lib "Miscellaneous Devices") (part "Res1"))
    )
    (comp (ref "R107")
      (value "2.2K")
      (footprint "c0805")
      (description "Resistor")
      (fields (field (name "PUBLISHER") "Altium Limited"))
      (libsource (lib "Miscellaneous Devices") (part "Res1"))
    )
    (comp (ref "R108")
      (value "220")
      (footprint "c0805")
      (description "Resistor")
      (fields (field (name "PUBLISHER") "Altium Limited"))
      (libsource (lib "Miscellaneous Devices") (part "Res1"))
    )
    (comp (ref "R109")
      (value "220")
      (footprint "c0805")
      (description "Resistor")
      (fields (field (name "PUBLISHER") "Altium Limited"))
      (libsource (lib "Miscellaneous Devices") (part "Res1"))
    )
    (comp (ref "S2")
      (value "SW DIP-3")
      (footprint "DIP-6")
      (description "DIP Switch, 3 Position, SPST")
      (fields (field (name "PUBLISHER") "Altium Limited"))
      (libsource (lib "Miscellaneous Devices") (part "SW DIP-3"))
    )
    (comp (ref "SW1")
      (value "Tact Switch")
      (footprint "TUCHSWITCH_SMD_2")
      (description "Swich")
      (fields (field (name "DESIGNER") "ziatbt@gmail.com") (field (name "DESIGNED") "19-October-2009"))
      (libsource (lib "Z.I.A Components") (part "Tak Switch"))
    )
    (comp (ref "SW2")
      (value "SW-PB")
      (footprint "TUCHSWITCH_SMD_2")
      (description "Switch")
      (fields (field (name "PUBLISHER") "Altium Limited"))
      (libsource (lib "Miscellaneous Devices") (part "SW-PB"))
    )
    (comp (ref "U1")
      (value "STM32F407ZGT6J")
      (footprint "STM-LQFP144_N")
      (fields (field (name "MANUFACTURER") "STMicroelectronics"))
      (libsource (lib "STMicroelectronics STM32 F4") (part "STM32F407ZGT6J"))
    )
    (comp (ref "U2")
      (value "DP83848CVV/NOPB")
      (footprint "QFP50P900X900X160-49N")
      (libsource (lib "DP83848CVV_NOPB") (part "DP83848CVV/NOPB"))
    )
    (comp (ref "U3")
      (value "REG1117-3.3")
      (footprint "ZZ311")
      (description "800mA and 1A Low Dropout Positive Regulator 2.85V, 3.3V, 5V, and Adjustable")
      (fields (field (name "PUBLISHER") "Altium Limited"))
      (libsource (lib "BB Power Mgt Voltage Regulator") (part "REG1117-3.3"))
    )
    (comp (ref "U4")
      (value "OSC-50.0000MHz")
      (footprint "XTAL-5*7")
      (libsource (lib "My-SCH") (part "XTALL-24.0000"))
    )
    (comp (ref "Y1")
      (value "25MHz")
      (footprint "XTAL - smd (2 Pad Crystal Oscilator)")
      (description "Crystal Oscillator")
      (fields (field (name "PUBLISHER") "Altium Limited"))
      (libsource (lib "WIZ550WEB") (part "XTAL"))
    )
  )
  (nets
    (net (code "1") (name "/4.5-6V") (class "Default")
      (node (ref "F1") (pin "1") (pinfunction "1_1") (pintype "passive"))
      (node (ref "P7") (pin "1") (pinfunction "1_1") (pintype "passive"))
    )
    (net (code "2") (name "/50MHz_ETH") (class "Default")
      (node (ref "R102") (pin "1") (pinfunction "1_1") (pintype "passive"))
      (node (ref "U2") (pin "34") (pinfunction "X1_34") (pintype "input"))
    )
    (net (code "3") (name "/ETH_CRS_DV") (class "Default")
      (node (ref "R25") (pin "1") (pinfunction "1_1") (pintype "passive"))
      (node (ref "U2") (pin "40") (pinfunction "CRS/CRS_DV/LED_CFG_40") (pintype "output"))
    )
    (net (code "4") (name "/ETH_MDC") (class "Default")
      (node (ref "R45") (pin "2") (pinfunction "2_2") (pintype "passive"))
      (node (ref "U2") (pin "31") (pinfunction "MDC_31") (pintype "input"))
    )
    (net (code "5") (name "/ETH_MDIO") (class "Default")
      (node (ref "R80") (pin "1") (pinfunction "1_1") (pintype "passive"))
      (node (ref "R9") (pin "2") (pinfunction "2_2") (pintype "passive"))
      (node (ref "U2") (pin "30") (pinfunction "MDIO_30") (pintype "bidirectional"))
    )
    (net (code "6") (name "/ETH_REF_CLK") (class "Default")
      (node (ref "U1") (pin "35") (pinfunction "PA1_35") (pintype "bidirectional"))
      (node (ref "U2") (pin "25") (pinfunction "CLK_OUT_25") (pintype "output"))
    )
    (net (code "7") (name "/ETH_RXD0") (class "Default")
      (node (ref "R52") (pin "2") (pinfunction "2_2") (pintype "passive"))
      (node (ref "U2") (pin "43") (pinfunction "RXD_0/PHYAD1_43") (pintype "output"))
    )
    (net (code "8") (name "/ETH_RXD1") (class "Default")
      (node (ref "R55") (pin "2") (pinfunction "2_2") (pintype "passive"))
      (node (ref "U2") (pin "44") (pinfunction "RXD_1/PHYAD2_44") (pintype "output"))
    )
    (net (code "9") (name "/ETH_TXD0") (class "Default")
      (node (ref "R36") (pin "2") (pinfunction "2_2") (pintype "passive"))
      (node (ref "U2") (pin "3") (pinfunction "TXD_0_3") (pintype "input"))
    )
    (net (code "10") (name "/ETH_TXD1") (class "Default")
      (node (ref "R38") (pin "2") (pinfunction "2_2") (pintype "passive"))
      (node (ref "U2") (pin "4") (pinfunction "TXD_1_4") (pintype "input"))
    )
    (net (code "11") (name "/ETH_TXDEN") (class "Default")
      (node (ref "R34") (pin "2") (pinfunction "2_2") (pintype "passive"))
      (node (ref "U2") (pin "2") (pinfunction "TX_EN_2") (pintype "input"))
    )
    (net (code "12") (name "/GLED-") (class "Default")
      (node (ref "P8") (pin "10") (pinfunction "GRN-_10") (pintype "passive"))
      (node (ref "R108") (pin "1") (pinfunction "1_1") (pintype "passive"))
    )
    (net (code "13") (name "/ISP RxD") (class "Default")
      (node (ref "P5") (pin "1") (pinfunction "1_1") (pintype "passive"))
      (node (ref "U1") (pin "101") (pinfunction "PA9_101") (pintype "bidirectional"))
    )
    (net (code "14") (name "/ISP TxD") (class "Default")
      (node (ref "P5") (pin "3") (pinfunction "3_3") (pintype "passive"))
      (node (ref "U1") (pin "102") (pinfunction "PA10_102") (pintype "bidirectional"))
    )
    (net (code "15") (name "/ISP-BOOT") (class "Default")
      (node (ref "R88") (pin "1") (pinfunction "1_1") (pintype "passive"))
      (node (ref "R91") (pin "2") (pinfunction "2_2") (pintype "passive"))
      (node (ref "U1") (pin "138") (pinfunction "BOOT0_138") (pintype "input"))
    )
    (net (code "16") (name "/LED0") (class "Default")
      (node (ref "D1") (pin "1") (pinfunction "A_1") (pintype "passive"))
      (node (ref "U1") (pin "140") (pinfunction "PB9_140") (pintype "bidirectional"))
    )
    (net (code "17") (name "/LED1") (class "Default")
      (node (ref "D2") (pin "1") (pinfunction "A_1") (pintype "passive"))
      (node (ref "U1") (pin "139") (pinfunction "PB8_139") (pintype "bidirectional"))
    )
    (net (code "18") (name "/LED2") (class "Default")
      (node (ref "D3") (pin "1") (pinfunction "A_1") (pintype "passive"))
      (node (ref "U1") (pin "112") (pinfunction "PC11_112") (pintype "bidirectional"))
    )
    (net (code "19") (name "/LED3") (class "Default")
      (node (ref "D4") (pin "1") (pinfunction "A_1") (pintype "passive"))
      (node (ref "U1") (pin "113") (pinfunction "PC12_113") (pintype "bidirectional"))
    )
    (net (code "20") (name "/LED_ACT") (class "Default")
      (node (ref "R106") (pin "1") (pinfunction "1_1") (pintype "passive"))
      (node (ref "R108") (pin "2") (pinfunction "2_2") (pintype "passive"))
      (node (ref "U2") (pin "26") (pinfunction "LED_ACT/COL/AN_EN_26") (pintype "output"))
    )
    (net (code "21") (name "/LED_LINK") (class "Default")
      (node (ref "R107") (pin "1") (pinfunction "1_1") (pintype "passive"))
      (node (ref "R109") (pin "2") (pinfunction "2_2") (pintype "passive"))
      (node (ref "U2") (pin "28") (pinfunction "LED_LINK/AN0_28") (pintype "output"))
    )
    (net (code "22") (name "/LED_SPEED") (class "Default")
      (node (ref "R94") (pin "2") (pinfunction "2_2") (pintype "passive"))
      (node (ref "U2") (pin "27") (pinfunction "LED_SPEED/AN1_27") (pintype "output"))
    )
    (net (code "23") (name "/MII_MODE") (class "Default")
      (node (ref "R95") (pin "1") (pinfunction "1_1") (pintype "passive"))
      (node (ref "U2") (pin "39") (pinfunction "RX_DV/MII_MODE_39") (pintype "output"))
    )
    (net (code "24") (name "/NRST") (class "Default")
      (node (ref "C22") (pin "1") (pinfunction "+_1") (pintype "passive"))
      (node (ref "R85") (pin "1") (pinfunction "1_1") (pintype "passive"))
      (node (ref "SW1") (pin "1") (pinfunction "1_1") (pintype "passive"))
      (node (ref "U1") (pin "25") (pinfunction "NRST_25") (pintype "bidirectional"))
      (node (ref "U2") (pin "29") (pinfunction "RESET_N_29") (pintype "input"))
    )
    (net (code "25") (name "/PA8") (class "Default")
      (node (ref "P4") (pin "17") (pinfunction "17_17") (pintype "passive"))
      (node (ref "R17") (pin "1") (pinfunction "1_1") (pintype "passive"))
    )
    (net (code "26") (name "/PB0") (class "Default")
      (node (ref "P3") (pin "5") (pinfunction "5_5") (pintype "passive"))
      (node (ref "R3") (pin "2") (pinfunction "2_2") (pintype "passive"))
    )
    (net (code "27") (name "/PB1") (class "Default")
      (node (ref "P3") (pin "6") (pinfunction "6_6") (pintype "passive"))
      (node (ref "R6") (pin "2") (pinfunction "2_2") (pintype "passive"))
    )
    (net (code "28") (name "/PB2") (class "Default")
      (node (ref "P3") (pin "7") (pinfunction "7_7") (pintype "passive"))
      (node (ref "R10") (pin "2") (pinfunction "2_2") (pintype "passive"))
    )
    (net (code "29") (name "/PB3") (class "Default")
      (node (ref "P1") (pin "18") (pinfunction "18_18") (pintype "passive"))
      (node (ref "R13") (pin "2") (pinfunction "2_2") (pintype "passive"))
    )
    (net (code "30") (name "/PD0") (class "Default")
      (node (ref "P1") (pin "3") (pinfunction "3_3") (pintype "passive"))
      (node (ref "R42") (pin "2") (pinfunction "2_2") (pintype "passive"))
    )
    (net (code "31") (name "/PD1") (class "Default")
      (node (ref "P1") (pin "4") (pinfunction "4_4") (pintype "passive"))
      (node (ref "R46") (pin "2") (pinfunction "2_2") (pintype "passive"))
    )
    (net (code "32") (name "/PD2") (class "Default")
      (node (ref "P1") (pin "5") (pinfunction "5_5") (pintype "passive"))
      (node (ref "R48") (pin "2") (pinfunction "2_2") (pintype "passive"))
    )
    (net (code "33") (name "/PD3") (class "Default")
      (node (ref "P1") (pin "6") (pinfunction "6_6") (pintype "passive"))
      (node (ref "R50") (pin "2") (pinfunction "2_2") (pintype "passive"))
    )
    (net (code "34") (name "/PD4") (class "Default")
      (node (ref "P1") (pin "7") (pinfunction "7_7") (pintype "passive"))
      (node (ref "R53") (pin "2") (pinfunction "2_2") (pintype "passive"))
    )
    (net (code "35") (name "/PD5") (class "Default")
      (node (ref "P1") (pin "8") (pinfunction "8_8") (pintype "passive"))
      (node (ref "R56") (pin "2") (pinfunction "2_2") (pintype "passive"))
    )
    (net (code "36") (name "/PD6") (class "Default")
      (node (ref "P1") (pin "9") (pinfunction "9_9") (pintype "passive"))
      (node (ref "R59") (pin "2") (pinfunction "2_2") (pintype "passive"))
    )
    (net (code "37") (name "/PD7") (class "Default")
      (node (ref "P1") (pin "10") (pinfunction "10_10") (pintype "passive"))
      (node (ref "R61") (pin "2") (pinfunction "2_2") (pintype "passive"))
    )
    (net (code "38") (name "/PD8") (class "Default")
      (node (ref "P4") (pin "3") (pinfunction "3_3") (pintype "passive"))
      (node (ref "R63") (pin "2") (pinfunction "2_2") (pintype "passive"))
    )
    (net (code "39") (name "/PD9") (class "Default")
      (node (ref "P4") (pin "4") (pinfunction "4_4") (pintype "passive"))
      (node (ref "R65") (pin "2") (pinfunction "2_2") (pintype "passive"))
    )
    (net (code "40") (name "/PD10") (class "Default")
      (node (ref "P4") (pin "5") (pinfunction "5_5") (pintype "passive"))
      (node (ref "R68") (pin "2") (pinfunction "2_2") (pintype "passive"))
    )
    (net (code "41") (name "/PD11") (class "Default")
      (node (ref "P4") (pin "6") (pinfunction "6_6") (pintype "passive"))
      (node (ref "R70") (pin "2") (pinfunction "2_2") (pintype "passive"))
    )
    (net (code "42") (name "/PD12") (class "Default")
      (node (ref "P4") (pin "7") (pinfunction "7_7") (pintype "passive"))
      (node (ref "R72") (pin "2") (pinfunction "2_2") (pintype "passive"))
    )
    (net (code "43") (name "/PD13") (class "Default")
      (node (ref "P4") (pin "8") (pinfunction "8_8") (pintype "passive"))
      (node (ref "R74") (pin "2") (pinfunction "2_2") (pintype "passive"))
    )
    (net (code "44") (name "/PD14") (class "Default")
      (node (ref "P4") (pin "9") (pinfunction "9_9") (pintype "passive"))
      (node (ref "R77") (pin "2") (pinfunction "2_2") (pintype "passive"))
    )
    (net (code "45") (name "/PD15") (class "Default")
      (node (ref "P4") (pin "10") (pinfunction "10_10") (pintype "passive"))
      (node (ref "R79") (pin "2") (pinfunction "2_2") (pintype "passive"))
    )
    (net (code "46") (name "/PE0") (class "Default")
      (node (ref "P2") (pin "18") (pinfunction "18_18") (pintype "passive"))
      (node (ref "R1") (pin "1") (pinfunction "1_1") (pintype "passive"))
    )
    (net (code "47") (name "/PE1") (class "Default")
      (node (ref "P2") (pin "17") (pinfunction "17_17") (pintype "passive"))
      (node (ref "R4") (pin "1") (pinfunction "1_1") (pintype "passive"))
    )
    (net (code "48") (name "/PE2") (class "Default")
      (node (ref "P2") (pin "16") (pinfunction "16_16") (pintype "passive"))
      (node (ref "R7") (pin "1") (pinfunction "1_1") (pintype "passive"))
    )
    (net (code "49") (name "/PE3") (class "Default")
      (node (ref "P2") (pin "15") (pinfunction "15_15") (pintype "passive"))
      (node (ref "R11") (pin "1") (pinfunction "1_1") (pintype "passive"))
    )
    (net (code "50") (name "/PE4") (class "Default")
      (node (ref "P2") (pin "14") (pinfunction "14_14") (pintype "passive"))
      (node (ref "R14") (pin "1") (pinfunction "1_1") (pintype "passive"))
    )
    (net (code "51") (name "/PE5") (class "Default")
      (node (ref "P2") (pin "13") (pinfunction "13_13") (pintype "passive"))
      (node (ref "R18") (pin "1") (pinfunction "1_1") (pintype "passive"))
    )
    (net (code "52") (name "/PE6") (class "Default")
      (node (ref "P2") (pin "12") (pinfunction "12_12") (pintype "passive"))
      (node (ref "R21") (pin "1") (pinfunction "1_1") (pintype "passive"))
    )
    (net (code "53") (name "/PE7") (class "Default")
      (node (ref "P3") (pin "15") (pinfunction "15_15") (pintype "passive"))
      (node (ref "R23") (pin "1") (pinfunction "1_1") (pintype "passive"))
    )
    (net (code "54") (name "/PE8") (class "Default")
      (node (ref "P3") (pin "16") (pinfunction "16_16") (pintype "passive"))
      (node (ref "R26") (pin "1") (pinfunction "1_1") (pintype "passive"))
    )
    (net (code "55") (name "/PE9") (class "Default")
      (node (ref "P3") (pin "17") (pinfunction "17_17") (pintype "passive"))
      (node (ref "R28") (pin "1") (pinfunction "1_1") (pintype "passive"))
    )
    (net (code "56") (name "/PE10") (class "Default")
      (node (ref "P3") (pin "18") (pinfunction "18_18") (pintype "passive"))
      (node (ref "R30") (pin "1") (pinfunction "1_1") (pintype "passive"))
    )
    (net (code "57") (name "/PF0") (class "Default")
      (node (ref "P2") (pin "11") (pinfunction "11_11") (pintype "passive"))
      (node (ref "R2") (pin "2") (pinfunction "2_2") (pintype "passive"))
    )
    (net (code "58") (name "/PF1") (class "Default")
      (node (ref "P2") (pin "10") (pinfunction "10_10") (pintype "passive"))
      (node (ref "R5") (pin "2") (pinfunction "2_2") (pintype "passive"))
    )
    (net (code "59") (name "/PF2") (class "Default")
      (node (ref "P2") (pin "9") (pinfunction "9_9") (pintype "passive"))
      (node (ref "R8") (pin "2") (pinfunction "2_2") (pintype "passive"))
    )
    (net (code "60") (name "/PF3") (class "Default")
      (node (ref "P2") (pin "8") (pinfunction "8_8") (pintype "passive"))
      (node (ref "R12") (pin "2") (pinfunction "2_2") (pintype "passive"))
    )
    (net (code "61") (name "/PF4") (class "Default")
      (node (ref "P2") (pin "7") (pinfunction "7_7") (pintype "passive"))
      (node (ref "R15") (pin "2") (pinfunction "2_2") (pintype "passive"))
    )
    (net (code "62") (name "/PF5") (class "Default")
      (node (ref "P2") (pin "6") (pinfunction "6_6") (pintype "passive"))
      (node (ref "R19") (pin "2") (pinfunction "2_2") (pintype "passive"))
    )
    (net (code "63") (name "/PF6") (class "Default")
      (node (ref "P2") (pin "5") (pinfunction "5_5") (pintype "passive"))
      (node (ref "R22") (pin "2") (pinfunction "2_2") (pintype "passive"))
    )
    (net (code "64") (name "/PF7") (class "Default")
      (node (ref "P2") (pin "4") (pinfunction "4_4") (pintype "passive"))
      (node (ref "R24") (pin "2") (pinfunction "2_2") (pintype "passive"))
    )
    (net (code "65") (name "/PF8") (class "Default")
      (node (ref "P2") (pin "3") (pinfunction "3_3") (pintype "passive"))
      (node (ref "R27") (pin "2") (pinfunction "2_2") (pintype "passive"))
    )
    (net (code "66") (name "/PF9") (class "Default")
      (node (ref "P3") (pin "3") (pinfunction "3_3") (pintype "passive"))
      (node (ref "R29") (pin "2") (pinfunction "2_2") (pintype "passive"))
    )
    (net (code "67") (name "/PF10") (class "Default")
      (node (ref "P3") (pin "4") (pinfunction "4_4") (pintype "passive"))
      (node (ref "R31") (pin "2") (pinfunction "2_2") (pintype "passive"))
    )
    (net (code "68") (name "/PF11") (class "Default")
      (node (ref "P3") (pin "8") (pinfunction "8_8") (pintype "passive"))
      (node (ref "R33") (pin "2") (pinfunction "2_2") (pintype "passive"))
    )
    (net (code "69") (name "/PF12") (class "Default")
      (node (ref "P3") (pin "9") (pinfunction "9_9") (pintype "passive"))
      (node (ref "R35") (pin "2") (pinfunction "2_2") (pintype "passive"))
    )
    (net (code "70") (name "/PF13") (class "Default")
      (node (ref "P3") (pin "10") (pinfunction "10_10") (pintype "passive"))
      (node (ref "R37") (pin "2") (pinfunction "2_2") (pintype "passive"))
    )
    (net (code "71") (name "/PF14") (class "Default")
      (node (ref "P3") (pin "11") (pinfunction "11_11") (pintype "passive"))
      (node (ref "R39") (pin "2") (pinfunction "2_2") (pintype "passive"))
    )
    (net (code "72") (name "/PF15") (class "Default")
      (node (ref "P3") (pin "12") (pinfunction "12_12") (pintype "passive"))
      (node (ref "R40") (pin "2") (pinfunction "2_2") (pintype "passive"))
    )
    (net (code "73") (name "/PG0") (class "Default")
      (node (ref "P3") (pin "13") (pinfunction "13_13") (pintype "passive"))
      (node (ref "R41") (pin "1") (pinfunction "1_1") (pintype "passive"))
    )
    (net (code "74") (name "/PG1") (class "Default")
      (node (ref "P3") (pin "14") (pinfunction "14_14") (pintype "passive"))
      (node (ref "R43") (pin "1") (pinfunction "1_1") (pintype "passive"))
    )
    (net (code "75") (name "/PG2") (class "Default")
      (node (ref "P4") (pin "11") (pinfunction "11_11") (pintype "passive"))
      (node (ref "R47") (pin "1") (pinfunction "1_1") (pintype "passive"))
    )
    (net (code "76") (name "/PG3") (class "Default")
      (node (ref "P4") (pin "12") (pinfunction "12_12") (pintype "passive"))
      (node (ref "R49") (pin "1") (pinfunction "1_1") (pintype "passive"))
    )
    (net (code "77") (name "/PG4") (class "Default")
      (node (ref "P4") (pin "13") (pinfunction "13_13") (pintype "passive"))
      (node (ref "R51") (pin "1") (pinfunction "1_1") (pintype "passive"))
    )
    (net (code "78") (name "/PG5") (class "Default")
      (node (ref "P4") (pin "14") (pinfunction "14_14") (pintype "passive"))
      (node (ref "R54") (pin "1") (pinfunction "1_1") (pintype "passive"))
    )
    (net (code "79") (name "/PG6") (class "Default")
      (node (ref "P4") (pin "15") (pinfunction "15_15") (pintype "passive"))
      (node (ref "R57") (pin "1") (pinfunction "1_1") (pintype "passive"))
    )
    (net (code "80") (name "/PG7") (class "Default")
      (node (ref "P4") (pin "16") (pinfunction "16_16") (pintype "passive"))
      (node (ref "R60") (pin "1") (pinfunction "1_1") (pintype "passive"))
    )
    (net (code "81") (name "/PG8") (class "Default")
      (node (ref "P4") (pin "18") (pinfunction "18_18") (pintype "passive"))
      (node (ref "R62") (pin "1") (pinfunction "1_1") (pintype "passive"))
    )
    (net (code "82") (name "/PG9") (class "Default")
      (node (ref "P1") (pin "11") (pinfunction "11_11") (pintype "passive"))
      (node (ref "R64") (pin "1") (pinfunction "1_1") (pintype "passive"))
    )
    (net (code "83") (name "/PG10") (class "Default")
      (node (ref "P1") (pin "12") (pinfunction "12_12") (pintype "passive"))
      (node (ref "R66") (pin "1") (pinfunction "1_1") (pintype "passive"))
    )
    (net (code "84") (name "/PG11") (class "Default")
      (node (ref "P1") (pin "13") (pinfunction "13_13") (pintype "passive"))
      (node (ref "R69") (pin "1") (pinfunction "1_1") (pintype "passive"))
    )
    (net (code "85") (name "/PG12") (class "Default")
      (node (ref "P1") (pin "14") (pinfunction "14_14") (pintype "passive"))
      (node (ref "R71") (pin "1") (pinfunction "1_1") (pintype "passive"))
    )
    (net (code "86") (name "/PG13") (class "Default")
      (node (ref "P1") (pin "15") (pinfunction "15_15") (pintype "passive"))
      (node (ref "R73") (pin "1") (pinfunction "1_1") (pintype "passive"))
    )
    (net (code "87") (name "/PG14") (class "Default")
      (node (ref "P1") (pin "16") (pinfunction "16_16") (pintype "passive"))
      (node (ref "R76") (pin "1") (pinfunction "1_1") (pintype "passive"))
    )
    (net (code "88") (name "/PG15") (class "Default")
      (node (ref "P1") (pin "17") (pinfunction "17_17") (pintype "passive"))
      (node (ref "R78") (pin "1") (pinfunction "1_1") (pintype "passive"))
    )
    (net (code "89") (name "/RJ45RD+") (class "Default")
      (node (ref "P8") (pin "3") (pinfunction "RD+_3") (pintype "passive"))
      (node (ref "R100") (pin "1") (pinfunction "1_1") (pintype "passive"))
      (node (ref "U2") (pin "14") (pinfunction "RD+_14") (pintype "bidirectional"))
    )
    (net (code "90") (name "/RJ45RD-") (class "Default")
      (node (ref "P8") (pin "6") (pinfunction "RD-_6") (pintype "passive"))
      (node (ref "R101") (pin "1") (pinfunction "1_1") (pintype "passive"))
      (node (ref "U2") (pin "13") (pinfunction "RD-_13") (pintype "bidirectional"))
    )
    (net (code "91") (name "/RJ45TD+") (class "Default")
      (node (ref "P8") (pin "1") (pinfunction "TD+_1") (pintype "passive"))
      (node (ref "R97") (pin "1") (pinfunction "1_1") (pintype "passive"))
      (node (ref "U2") (pin "17") (pinfunction "TD+_17") (pintype "bidirectional"))
    )
    (net (code "92") (name "/RJ45TD-") (class "Default")
      (node (ref "P8") (pin "2") (pinfunction "TD-_2") (pintype "passive"))
      (node (ref "R98") (pin "1") (pinfunction "1_1") (pintype "passive"))
      (node (ref "U2") (pin "16") (pinfunction "TD-_16") (pintype "bidirectional"))
    )
    (net (code "93") (name "/SD_CS") (class "Default")
      (node (ref "J1") (pin "2") (pinfunction "CD/DAT3_2") (pintype "passive"))
      (node (ref "R16") (pin "1") (pinfunction "1_1") (pintype "passive"))
    )
    (net (code "94") (name "/SD_MISO") (class "Default")
      (node (ref "J1") (pin "7") (pinfunction "DAT0_7") (pintype "passive"))
      (node (ref "U1") (pin "134") (pinfunction "PB4(NJTRST)_134") (pintype "bidirectional"))
    )
    (net (code "95") (name "/SD_MOSI") (class "Default")
      (node (ref "J1") (pin "3") (pinfunction "CMD_3") (pintype "passive"))
      (node (ref "U1") (pin "135") (pinfunction "PB5_135") (pintype "bidirectional"))
    )
    (net (code "96") (name "/SD_SCLK") (class "Default")
      (node (ref "J1") (pin "5") (pinfunction "CLK_5") (pintype "passive"))
      (node (ref "U1") (pin "41") (pinfunction "PA5_41") (pintype "bidirectional"))
    )
    (net (code "97") (name "/SNI_MODE") (class "Default")
      (node (ref "R104") (pin "2") (pinfunction "2_2") (pintype "passive"))
      (node (ref "U2") (pin "6") (pinfunction "TXD_3/SNI_MODE_6") (pintype "input"))
    )
    (net (code "98") (name "/SW1") (class "Default")
      (node (ref "S2") (pin "1") (pinfunction "A1_1") (pintype "passive"))
      (node (ref "U1") (pin "68") (pinfunction "PE15_68") (pintype "bidirectional"))
    )
    (net (code "99") (name "/SW2") (class "Default")
      (node (ref "S2") (pin "2") (pinfunction "A2_2") (pintype "passive"))
      (node (ref "U1") (pin "67") (pinfunction "PE14_67") (pintype "bidirectional"))
    )
    (net (code "100") (name "/SW3") (class "Default")
      (node (ref "S2") (pin "3") (pinfunction "A3_3") (pintype "passive"))
      (node (ref "U1") (pin "66") (pinfunction "PE13_66") (pintype "bidirectional"))
    )
    (net (code "101") (name "/SW4") (class "Default")
      (node (ref "SW2") (pin "1") (pinfunction "1_1") (pintype "passive"))
      (node (ref "U1") (pin "65") (pinfunction "PE12_65") (pintype "bidirectional"))
    )
    (net (code "102") (name "/TCK") (class "Default")
      (node (ref "P6") (pin "2") (pinfunction "2_2") (pintype "passive"))
      (node (ref "R92") (pin "1") (pinfunction "1_1") (pintype "passive"))
      (node (ref "U1") (pin "109") (pinfunction "PA14(JTCK-SWCLK)_109") (pintype "bidirectional"))
    )
    (net (code "103") (name "/TMS") (class "Default")
      (node (ref "P6") (pin "3") (pinfunction "3_3") (pintype "passive"))
      (node (ref "R87") (pin "1") (pinfunction "1_1") (pintype "passive"))
      (node (ref "U1") (pin "105") (pinfunction "PA13(JTMS-SWDIO)_105") (pintype "bidirectional"))
    )
    (net (code "104") (name "/YLED-") (class "Default")
      (node (ref "P8") (pin "11") (pinfunction "YLW-_11") (pintype "passive"))
      (node (ref "R109") (pin "1") (pinfunction "1_1") (pintype "passive"))
    )
    (net (code "105") (name "GND") (class "Default")
      (node (ref "C1") (pin "2") (pinfunction "-_2") (pintype "passive"))
      (node (ref "C10") (pin "2") (pinfunction "-_2") (pintype "passive"))
      (node (ref "C13") (pin "2") (pinfunction "-_2") (pintype "passive"))
      (node (ref "C14") (pin "2") (pinfunction "-_2") (pintype "passive"))
      (node (ref "C15") (pin "2") (pinfunction "-_2") (pintype "passive"))
      (node (ref "C16") (pin "2") (pinfunction "-_2") (pintype "passive"))
      (node (ref "C17") (pin "2") (pinfunction "2_2") (pintype "passive"))
      (node (ref "C18") (pin "2") (pinfunction "-_2") (pintype "passive"))
      (node (ref "C19") (pin "2") (pinfunction "-_2") (pintype "passive"))
      (node (ref "C2") (pin "1") (pinfunction "+_1") (pintype "passive"))
      (node (ref "C20") (pin "2") (pinfunction "-_2") (pintype "passive"))
      (node (ref "C21") (pin "2") (pinfunction "-_2") (pintype "passive"))
      (node (ref "C22") (pin "2") (pinfunction "-_2") (pintype "passive"))
      (node (ref "C23") (pin "2") (pinfunction "2_2") (pintype "passive"))
      (node (ref "C24") (pin "2") (pinfunction "2_2") (pintype "passive"))
      (node (ref "C25") (pin "2") (pinfunction "2_2") (pintype "passive"))
      (node (ref "C26") (pin "2") (pinfunction "2_2") (pintype "passive"))
      (node (ref "C27") (pin "2") (pinfunction "2_2") (pintype "passive"))
      (node (ref "C28") (pin "2") (pinfunction "2_2") (pintype "passive"))
      (node (ref "C29") (pin "2") (pinfunction "2_2") (pintype "passive"))
      (node (ref "C3") (pin "1") (pinfunction "+_1") (pintype "passive"))
      (node (ref "C30") (pin "2") (pinfunction "2_2") (pintype "passive"))
      (node (ref "C31") (pin "2") (pinfunction "2_2") (pintype "passive"))
      (node (ref "C32") (pin "2") (pinfunction "2_2") (pintype "passive"))
      (node (ref "C33") (pin "2") (pinfunction "2_2") (pintype "passive"))
      (node (ref "C34") (pin "2") (pinfunction "2_2") (pintype "passive"))
      (node (ref "C35") (pin "2") (pinfunction "2_2") (pintype "passive"))
      (node (ref "C4") (pin "1") (pinfunction "+_1") (pintype "passive"))
      (node (ref "C5") (pin "2") (pinfunction "2_2") (pintype "passive"))
      (node (ref "C6") (pin "2") (pinfunction "-_2") (pintype "passive"))
      (node (ref "C7") (pin "2") (pinfunction "-_2") (pintype "passive"))
      (node (ref "C8") (pin "2") (pinfunction "-_2") (pintype "passive"))
      (node (ref "C9") (pin "2") (pinfunction "-_2") (pintype "passive"))
      (node (ref "D7") (pin "2") (pinfunction "K_2") (pintype "passive"))
      (node (ref "J1") (pin "10") (pinfunction "GND_10") (pintype "passive"))
      (node (ref "J1") (pin "11") (pinfunction "GND_11") (pintype "passive"))
      (node (ref "J1") (pin "12") (pinfunction "GND_12") (pintype "passive"))
      (node (ref "J1") (pin "13") (pinfunction "GND_13") (pintype "passive"))
      (node (ref "J1") (pin "6") (pinfunction "VSS_6") (pintype "passive"))
      (node (ref "P1") (pin "19") (pinfunction "19_19") (pintype "passive"))
      (node (ref "P1") (pin "2") (pinfunction "2_2") (pintype "passive"))
      (node (ref "P2") (pin "19") (pinfunction "19_19") (pintype "passive"))
      (node (ref "P2") (pin "20") (pinfunction "20_20") (pintype "passive"))
      (node (ref "P3") (pin "19") (pinfunction "19_19") (pintype "passive"))
      (node (ref "P3") (pin "20") (pinfunction "20_20") (pintype "passive"))
      (node (ref "P4") (pin "19") (pinfunction "19_19") (pintype "passive"))
      (node (ref "P4") (pin "20") (pinfunction "20_20") (pintype "passive"))
      (node (ref "P5") (pin "2") (pinfunction "2_2") (pintype "passive"))
      (node (ref "P6") (pin "1") (pinfunction "1_1") (pintype "passive"))
      (node (ref "P7") (pin "2") (pinfunction "2_2") (pintype "passive"))
      (node (ref "P8") (pin "13") (pinfunction "CH_GND_13") (pintype "passive"))
      (node (ref "P8") (pin "14") (pinfunction "GH_GND_14") (pintype "passive"))
      (node (ref "P8") (pin "8") (pinfunction "CHs_GND_8") (pintype "passive"))
      (node (ref "R104") (pin "1") (pinfunction "1_1") (pintype "passive"))
      (node (ref "R105") (pin "2") (pinfunction "2_2") (pintype "passive"))
      (node (ref "R84") (pin "2") (pinfunction "2_2") (pintype "passive"))
      (node (ref "R86") (pin "1") (pinfunction "1_1") (pintype "passive"))
      (node (ref "R89") (pin "2") (pinfunction "2_2") (pintype "passive"))
      (node (ref "R90") (pin "2") (pinfunction "2_2") (pintype "passive"))
      (node (ref "R91") (pin "1") (pinfunction "1_1") (pintype "passive"))
      (node (ref "R92") (pin "2") (pinfunction "2_2") (pintype "passive"))
      (node (ref "R93") (pin "2") (pinfunction "2_2") (pintype "passive"))
      (node (ref "S2") (pin "4") (pinfunction "B3_4") (pintype "passive"))
      (node (ref "S2") (pin "5") (pinfunction "B2_5") (pintype "passive"))
      (node (ref "S2") (pin "6") (pinfunction "B1_6") (pintype "passive"))
      (node (ref "SW1") (pin "2") (pinfunction "2_2") (pintype "passive"))
      (node (ref "SW2") (pin "2") (pinfunction "2_2") (pintype "passive"))
      (node (ref "U1") (pin "107") (pinfunction "VSS_107") (pintype "power_in"))
      (node (ref "U1") (pin "120") (pinfunction "VSS_120") (pintype "power_in"))
      (node (ref "U1") (pin "130") (pinfunction "VSS_130") (pintype "power_in"))
      (node (ref "U1") (pin "16") (pinfunction "VSS_16") (pintype "power_in"))
      (node (ref "U1") (pin "31") (pinfunction "VSSA_31") (pintype "power_in"))
      (node (ref "U1") (pin "38") (pinfunction "VSS_38") (pintype "power_in"))
      (node (ref "U1") (pin "51") (pinfunction "VSS_51") (pintype "power_in"))
      (node (ref "U1") (pin "61") (pinfunction "VSS_61") (pintype "power_in"))
      (node (ref "U1") (pin "83") (pinfunction "VSS_83") (pintype "power_in"))
      (node (ref "U1") (pin "94") (pinfunction "VSS_94") (pintype "power_in"))
      (node (ref "U2") (pin "15") (pinfunction "AGND_15_15") (pintype "power_in"))
      (node (ref "U2") (pin "19") (pinfunction "AGND_19_19") (pintype "power_in"))
      (node (ref "U2") (pin "35") (pinfunction "IOGND_35_35") (pintype "power_in"))
      (node (ref "U2") (pin "36") (pinfunction "DGND_36") (pintype "power_in"))
      (node (ref "U2") (pin "47") (pinfunction "IOGND_47_47") (pintype "power_in"))
      (node (ref "U3") (pin "1") (pinfunction "GND_1") (pintype "power_in"))
      (node (ref "U4") (pin "2") (pinfunction "GND_2") (pintype "power_in"))
    )
    (net (code "106") (name "Net-(C1-+)") (class "Default")
      (node (ref "C1") (pin "1") (pinfunction "+_1") (pintype "passive"))
      (node (ref "R44") (pin "2") (pinfunction "2_2") (pintype "passive"))
      (node (ref "U1") (pin "23") (pinfunction "PH0-OSC_IN(PH0)_23") (pintype "bidirectional"))
      (node (ref "Y1") (pin "2") (pinfunction "OSC2_2") (pintype "passive"))
    )
    (net (code "107") (name "Net-(C2--)") (class "Default")
      (node (ref "C2") (pin "2") (pinfunction "-_2") (pintype "passive"))
      (node (ref "R44") (pin "1") (pinfunction "1_1") (pintype "passive"))
      (node (ref "U1") (pin "24") (pinfunction "PH1-OSC_OUT(PH1)_24") (pintype "bidirectional"))
      (node (ref "Y1") (pin "1") (pinfunction "OSC1_1") (pintype "passive"))
    )
    (net (code "108") (name "Net-(C3--)") (class "Default")
      (node (ref "C3") (pin "2") (pinfunction "-_2") (pintype "passive"))
      (node (ref "U1") (pin "71") (pinfunction "VCAP_1_71") (pintype "power_in"))
    )
    (net (code "109") (name "Net-(C4--)") (class "Default")
      (node (ref "C4") (pin "2") (pinfunction "-_2") (pintype "passive"))
      (node (ref "U1") (pin "106") (pinfunction "VCAP_2_106") (pintype "power_in"))
    )
    (net (code "110") (name "Net-(D1-K)") (class "Default")
      (node (ref "D1") (pin "2") (pinfunction "K_2") (pintype "passive"))
      (node (ref "R86") (pin "2") (pinfunction "2_2") (pintype "passive"))
    )
    (net (code "111") (name "Net-(D2-K)") (class "Default")
      (node (ref "D2") (pin "2") (pinfunction "K_2") (pintype "passive"))
      (node (ref "R89") (pin "1") (pinfunction "1_1") (pintype "passive"))
    )
    (net (code "112") (name "Net-(D3-K)") (class "Default")
      (node (ref "D3") (pin "2") (pinfunction "K_2") (pintype "passive"))
      (node (ref "R90") (pin "1") (pinfunction "1_1") (pintype "passive"))
    )
    (net (code "113") (name "Net-(D4-K)") (class "Default")
      (node (ref "D4") (pin "2") (pinfunction "K_2") (pintype "passive"))
      (node (ref "R93") (pin "1") (pinfunction "1_1") (pintype "passive"))
    )
    (net (code "114") (name "Net-(D5-K)") (class "Default")
      (node (ref "D5") (pin "2") (pinfunction "K_2") (pintype "passive"))
      (node (ref "R94") (pin "1") (pinfunction "1_1") (pintype "passive"))
    )
    (net (code "115") (name "Net-(D7-A)") (class "Default")
      (node (ref "D7") (pin "1") (pinfunction "A_1") (pintype "passive"))
      (node (ref "R103") (pin "1") (pinfunction "1_1") (pintype "passive"))
    )
    (net (code "116") (name "Net-(R96-Pad2)") (class "Default")
      (node (ref "R96") (pin "2") (pinfunction "2_2") (pintype "passive"))
      (node (ref "U3") (pin "2") (pinfunction "OUT_2") (pintype "power_in"))
      (node (ref "U3") (pin "4") (pinfunction "OUT_4") (pintype "power_in"))
    )
    (net (code "117") (name "Net-(U1A-PA2)") (class "Default")
      (node (ref "R9") (pin "1") (pinfunction "1_1") (pintype "passive"))
      (node (ref "U1") (pin "36") (pinfunction "PA2_36") (pintype "bidirectional"))
    )
    (net (code "118") (name "Net-(U1A-PA4)") (class "Default")
      (node (ref "R16") (pin "2") (pinfunction "2_2") (pintype "passive"))
      (node (ref "U1") (pin "40") (pinfunction "PA4_40") (pintype "bidirectional"))
    )
    (net (code "119") (name "Net-(U1A-PA7)") (class "Default")
      (node (ref "R25") (pin "2") (pinfunction "2_2") (pintype "passive"))
      (node (ref "U1") (pin "43") (pinfunction "PA7_43") (pintype "bidirectional"))
    )
    (net (code "120") (name "Net-(U1A-PA8)") (class "Default")
      (node (ref "R17") (pin "2") (pinfunction "2_2") (pintype "passive"))
      (node (ref "U1") (pin "100") (pinfunction "PA8_100") (pintype "bidirectional"))
    )
    (net (code "121") (name "Net-(U1A-PB0)") (class "Default")
      (node (ref "R3") (pin "1") (pinfunction "1_1") (pintype "passive"))
      (node (ref "U1") (pin "46") (pinfunction "PB0_46") (pintype "bidirectional"))
    )
    (net (code "122") (name "Net-(U1A-PB1)") (class "Default")
      (node (ref "R6") (pin "1") (pinfunction "1_1") (pintype "passive"))
      (node (ref "U1") (pin "47") (pinfunction "PB1_47") (pintype "bidirectional"))
    )
    (net (code "123") (name "Net-(U1A-PB2-BOOT1(PB2))") (class "Default")
      (node (ref "R10") (pin "1") (pinfunction "1_1") (pintype "passive"))
      (node (ref "U1") (pin "48") (pinfunction "PB2-BOOT1(PB2)_48") (pintype "bidirectional"))
    )
    (net (code "124") (name "Net-(U1A-PB3(JTDO{slash}TRACESWO))") (class "Default")
      (node (ref "R13") (pin "1") (pinfunction "1_1") (pintype "passive"))
      (node (ref "U1") (pin "133") (pinfunction "PB3(JTDO/TRACESWO)_133") (pintype "bidirectional"))
    )
    (net (code "125") (name "Net-(U1A-PB11)") (class "Default")
      (node (ref "R34") (pin "1") (pinfunction "1_1") (pintype "passive"))
      (node (ref "U1") (pin "70") (pinfunction "PB11_70") (pintype "bidirectional"))
    )
    (net (code "126") (name "Net-(U1A-PB12)") (class "Default")
      (node (ref "R36") (pin "1") (pinfunction "1_1") (pintype "passive"))
      (node (ref "U1") (pin "73") (pinfunction "PB12_73") (pintype "bidirectional"))
    )
    (net (code "127") (name "Net-(U1A-PB13)") (class "Default")
      (node (ref "R38") (pin "1") (pinfunction "1_1") (pintype "passive"))
      (node (ref "U1") (pin "74") (pinfunction "PB13_74") (pintype "bidirectional"))
    )
    (net (code "128") (name "Net-(U1A-PC1)") (class "Default")
      (node (ref "R45") (pin "1") (pinfunction "1_1") (pintype "passive"))
      (node (ref "U1") (pin "27") (pinfunction "PC1_27") (pintype "bidirectional"))
    )
    (net (code "129") (name "Net-(U1A-PC4)") (class "Default")
      (node (ref "R52") (pin "1") (pinfunction "1_1") (pintype "passive"))
      (node (ref "U1") (pin "44") (pinfunction "PC4_44") (pintype "bidirectional"))
    )
    (net (code "130") (name "Net-(U1A-PC5)") (class "Default")
      (node (ref "R55") (pin "1") (pinfunction "1_1") (pintype "passive"))
      (node (ref "U1") (pin "45") (pinfunction "PC5_45") (pintype "bidirectional"))
    )
    (net (code "131") (name "Net-(U1A-PD0)") (class "Default")
      (node (ref "R42") (pin "1") (pinfunction "1_1") (pintype "passive"))
      (node (ref "U1") (pin "114") (pinfunction "PD0_114") (pintype "bidirectional"))
    )
    (net (code "132") (name "Net-(U1A-PD1)") (class "Default")
      (node (ref "R46") (pin "1") (pinfunction "1_1") (pintype "passive"))
      (node (ref "U1") (pin "115") (pinfunction "PD1_115") (pintype "bidirectional"))
    )
    (net (code "133") (name "Net-(U1A-PD2)") (class "Default")
      (node (ref "R48") (pin "1") (pinfunction "1_1") (pintype "passive"))
      (node (ref "U1") (pin "116") (pinfunction "PD2_116") (pintype "bidirectional"))
    )
    (net (code "134") (name "Net-(U1A-PD3)") (class "Default")
      (node (ref "R50") (pin "1") (pinfunction "1_1") (pintype "passive"))
      (node (ref "U1") (pin "117") (pinfunction "PD3_117") (pintype "bidirectional"))
    )
    (net (code "135") (name "Net-(U1A-PD4)") (class "Default")
      (node (ref "R53") (pin "1") (pinfunction "1_1") (pintype "passive"))
      (node (ref "U1") (pin "118") (pinfunction "PD4_118") (pintype "bidirectional"))
    )
    (net (code "136") (name "Net-(U1A-PD5)") (class "Default")
      (node (ref "R56") (pin "1") (pinfunction "1_1") (pintype "passive"))
      (node (ref "U1") (pin "119") (pinfunction "PD5_119") (pintype "bidirectional"))
    )
    (net (code "137") (name "Net-(U1A-PD6)") (class "Default")
      (node (ref "R59") (pin "1") (pinfunction "1_1") (pintype "passive"))
      (node (ref "U1") (pin "122") (pinfunction "PD6_122") (pintype "bidirectional"))
    )
    (net (code "138") (name "Net-(U1A-PD7)") (class "Default")
      (node (ref "R61") (pin "1") (pinfunction "1_1") (pintype "passive"))
      (node (ref "U1") (pin "123") (pinfunction "PD7_123") (pintype "bidirectional"))
    )
    (net (code "139") (name "Net-(U1A-PD8)") (class "Default")
      (node (ref "R63") (pin "1") (pinfunction "1_1") (pintype "passive"))
      (node (ref "U1") (pin "77") (pinfunction "PD8_77") (pintype "bidirectional"))
    )
    (net (code "140") (name "Net-(U1A-PD9)") (class "Default")
      (node (ref "R65") (pin "1") (pinfunction "1_1") (pintype "passive"))
      (node (ref "U1") (pin "78") (pinfunction "PD9_78") (pintype "bidirectional"))
    )
    (net (code "141") (name "Net-(U1A-PD10)") (class "Default")
      (node (ref "R68") (pin "1") (pinfunction "1_1") (pintype "passive"))
      (node (ref "U1") (pin "79") (pinfunction "PD10_79") (pintype "bidirectional"))
    )
    (net (code "142") (name "Net-(U1A-PD11)") (class "Default")
      (node (ref "R70") (pin "1") (pinfunction "1_1") (pintype "passive"))
      (node (ref "U1") (pin "80") (pinfunction "PD11_80") (pintype "bidirectional"))
    )
    (net (code "143") (name "Net-(U1A-PD12)") (class "Default")
      (node (ref "R72") (pin "1") (pinfunction "1_1") (pintype "passive"))
      (node (ref "U1") (pin "81") (pinfunction "PD12_81") (pintype "bidirectional"))
    )
    (net (code "144") (name "Net-(U1A-PD13)") (class "Default")
      (node (ref "R74") (pin "1") (pinfunction "1_1") (pintype "passive"))
      (node (ref "U1") (pin "82") (pinfunction "PD13_82") (pintype "bidirectional"))
    )
    (net (code "145") (name "Net-(U1A-PD14)") (class "Default")
      (node (ref "R77") (pin "1") (pinfunction "1_1") (pintype "passive"))
      (node (ref "U1") (pin "85") (pinfunction "PD14_85") (pintype "bidirectional"))
    )
    (net (code "146") (name "Net-(U1A-PD15)") (class "Default")
      (node (ref "R79") (pin "1") (pinfunction "1_1") (pintype "passive"))
      (node (ref "U1") (pin "86") (pinfunction "PD15_86") (pintype "bidirectional"))
    )
    (net (code "147") (name "Net-(U1B-PE0)") (class "Default")
      (node (ref "R1") (pin "2") (pinfunction "2_2") (pintype "passive"))
      (node (ref "U1") (pin "141") (pinfunction "PE0_141") (pintype "bidirectional"))
    )
    (net (code "148") (name "Net-(U1B-PE1)") (class "Default")
      (node (ref "R4") (pin "2") (pinfunction "2_2") (pintype "passive"))
      (node (ref "U1") (pin "142") (pinfunction "PE1_142") (pintype "bidirectional"))
    )
    (net (code "149") (name "Net-(U1B-PE2)") (class "Default")
      (node (ref "R7") (pin "2") (pinfunction "2_2") (pintype "passive"))
      (node (ref "U1") (pin "1") (pinfunction "PE2_1") (pintype "bidirectional"))
    )
    (net (code "150") (name "Net-(U1B-PE3)") (class "Default")
      (node (ref "R11") (pin "2") (pinfunction "2_2") (pintype "passive"))
      (node (ref "U1") (pin "2") (pinfunction "PE3_2") (pintype "bidirectional"))
    )
    (net (code "151") (name "Net-(U1B-PE4)") (class "Default")
      (node (ref "R14") (pin "2") (pinfunction "2_2") (pintype "passive"))
      (node (ref "U1") (pin "3") (pinfunction "PE4_3") (pintype "bidirectional"))
    )
    (net (code "152") (name "Net-(U1B-PE5)") (class "Default")
      (node (ref "R18") (pin "2") (pinfunction "2_2") (pintype "passive"))
      (node (ref "U1") (pin "4") (pinfunction "PE5_4") (pintype "bidirectional"))
    )
    (net (code "153") (name "Net-(U1B-PE6)") (class "Default")
      (node (ref "R21") (pin "2") (pinfunction "2_2") (pintype "passive"))
      (node (ref "U1") (pin "5") (pinfunction "PE6_5") (pintype "bidirectional"))
    )
    (net (code "154") (name "Net-(U1B-PE7)") (class "Default")
      (node (ref "R23") (pin "2") (pinfunction "2_2") (pintype "passive"))
      (node (ref "U1") (pin "58") (pinfunction "PE7_58") (pintype "bidirectional"))
    )
    (net (code "155") (name "Net-(U1B-PE8)") (class "Default")
      (node (ref "R26") (pin "2") (pinfunction "2_2") (pintype "passive"))
      (node (ref "U1") (pin "59") (pinfunction "PE8_59") (pintype "bidirectional"))
    )
    (net (code "156") (name "Net-(U1B-PE9)") (class "Default")
      (node (ref "R28") (pin "2") (pinfunction "2_2") (pintype "passive"))
      (node (ref "U1") (pin "60") (pinfunction "PE9_60") (pintype "bidirectional"))
    )
    (net (code "157") (name "Net-(U1B-PE10)") (class "Default")
      (node (ref "R30") (pin "2") (pinfunction "2_2") (pintype "passive"))
      (node (ref "U1") (pin "63") (pinfunction "PE10_63") (pintype "bidirectional"))
    )
    (net (code "158") (name "Net-(U1B-PF0)") (class "Default")
      (node (ref "R2") (pin "1") (pinfunction "1_1") (pintype "passive"))
      (node (ref "U1") (pin "10") (pinfunction "PF0_10") (pintype "bidirectional"))
    )
    (net (code "159") (name "Net-(U1B-PF1)") (class "Default")
      (node (ref "R5") (pin "1") (pinfunction "1_1") (pintype "passive"))
      (node (ref "U1") (pin "11") (pinfunction "PF1_11") (pintype "bidirectional"))
    )
    (net (code "160") (name "Net-(U1B-PF2)") (class "Default")
      (node (ref "R8") (pin "1") (pinfunction "1_1") (pintype "passive"))
      (node (ref "U1") (pin "12") (pinfunction "PF2_12") (pintype "bidirectional"))
    )
    (net (code "161") (name "Net-(U1B-PF3)") (class "Default")
      (node (ref "R12") (pin "1") (pinfunction "1_1") (pintype "passive"))
      (node (ref "U1") (pin "13") (pinfunction "PF3_13") (pintype "bidirectional"))
    )
    (net (code "162") (name "Net-(U1B-PF4)") (class "Default")
      (node (ref "R15") (pin "1") (pinfunction "1_1") (pintype "passive"))
      (node (ref "U1") (pin "14") (pinfunction "PF4_14") (pintype "bidirectional"))
    )
    (net (code "163") (name "Net-(U1B-PF5)") (class "Default")
      (node (ref "R19") (pin "1") (pinfunction "1_1") (pintype "passive"))
      (node (ref "U1") (pin "15") (pinfunction "PF5_15") (pintype "bidirectional"))
    )
    (net (code "164") (name "Net-(U1B-PF6)") (class "Default")
      (node (ref "R22") (pin "1") (pinfunction "1_1") (pintype "passive"))
      (node (ref "U1") (pin "18") (pinfunction "PF6_18") (pintype "bidirectional"))
    )
    (net (code "165") (name "Net-(U1B-PF7)") (class "Default")
      (node (ref "R24") (pin "1") (pinfunction "1_1") (pintype "passive"))
      (node (ref "U1") (pin "19") (pinfunction "PF7_19") (pintype "bidirectional"))
    )
    (net (code "166") (name "Net-(U1B-PF8)") (class "Default")
      (node (ref "R27") (pin "1") (pinfunction "1_1") (pintype "passive"))
      (node (ref "U1") (pin "20") (pinfunction "PF8_20") (pintype "bidirectional"))
    )
    (net (code "167") (name "Net-(U1B-PF9)") (class "Default")
      (node (ref "R29") (pin "1") (pinfunction "1_1") (pintype "passive"))
      (node (ref "U1") (pin "21") (pinfunction "PF9_21") (pintype "bidirectional"))
    )
    (net (code "168") (name "Net-(U1B-PF10)") (class "Default")
      (node (ref "R31") (pin "1") (pinfunction "1_1") (pintype "passive"))
      (node (ref "U1") (pin "22") (pinfunction "PF10_22") (pintype "bidirectional"))
    )
    (net (code "169") (name "Net-(U1B-PF11)") (class "Default")
      (node (ref "R33") (pin "1") (pinfunction "1_1") (pintype "passive"))
      (node (ref "U1") (pin "49") (pinfunction "PF11_49") (pintype "bidirectional"))
    )
    (net (code "170") (name "Net-(U1B-PF12)") (class "Default")
      (node (ref "R35") (pin "1") (pinfunction "1_1") (pintype "passive"))
      (node (ref "U1") (pin "50") (pinfunction "PF12_50") (pintype "bidirectional"))
    )
    (net (code "171") (name "Net-(U1B-PF13)") (class "Default")
      (node (ref "R37") (pin "1") (pinfunction "1_1") (pintype "passive"))
      (node (ref "U1") (pin "53") (pinfunction "PF13_53") (pintype "bidirectional"))
    )
    (net (code "172") (name "Net-(U1B-PF14)") (class "Default")
      (node (ref "R39") (pin "1") (pinfunction "1_1") (pintype "passive"))
      (node (ref "U1") (pin "54") (pinfunction "PF14_54") (pintype "bidirectional"))
    )
    (net (code "173") (name "Net-(U1B-PF15)") (class "Default")
      (node (ref "R40") (pin "1") (pinfunction "1_1") (pintype "passive"))
      (node (ref "U1") (pin "55") (pinfunction "PF15_55") (pintype "bidirectional"))
    )
    (net (code "174") (name "Net-(U1B-PG0)") (class "Default")
      (node (ref "R41") (pin "2") (pinfunction "2_2") (pintype "passive"))
      (node (ref "U1") (pin "56") (pinfunction "PG0_56") (pintype "bidirectional"))
    )
    (net (code "175") (name "Net-(U1B-PG1)") (class "Default")
      (node (ref "R43") (pin "2") (pinfunction "2_2") (pintype "passive"))
      (node (ref "U1") (pin "57") (pinfunction "PG1_57") (pintype "bidirectional"))
    )
    (net (code "176") (name "Net-(U1B-PG2)") (class "Default")
      (node (ref "R47") (pin "2") (pinfunction "2_2") (pintype "passive"))
      (node (ref "U1") (pin "87") (pinfunction "PG2_87") (pintype "bidirectional"))
    )
    (net (code "177") (name "Net-(U1B-PG3)") (class "Default")
      (node (ref "R49") (pin "2") (pinfunction "2_2") (pintype "passive"))
      (node (ref "U1") (pin "88") (pinfunction "PG3_88") (pintype "bidirectional"))
    )
    (net (code "178") (name "Net-(U1B-PG4)") (class "Default")
      (node (ref "R51") (pin "2") (pinfunction "2_2") (pintype "passive"))
      (node (ref "U1") (pin "89") (pinfunction "PG4_89") (pintype "bidirectional"))
    )
    (net (code "179") (name "Net-(U1B-PG5)") (class "Default")
      (node (ref "R54") (pin "2") (pinfunction "2_2") (pintype "passive"))
      (node (ref "U1") (pin "90") (pinfunction "PG5_90") (pintype "bidirectional"))
    )
    (net (code "180") (name "Net-(U1B-PG6)") (class "Default")
      (node (ref "R57") (pin "2") (pinfunction "2_2") (pintype "passive"))
      (node (ref "U1") (pin "91") (pinfunction "PG6_91") (pintype "bidirectional"))
    )
    (net (code "181") (name "Net-(U1B-PG7)") (class "Default")
      (node (ref "R60") (pin "2") (pinfunction "2_2") (pintype "passive"))
      (node (ref "U1") (pin "92") (pinfunction "PG7_92") (pintype "bidirectional"))
    )
    (net (code "182") (name "Net-(U1B-PG8)") (class "Default")
      (node (ref "R62") (pin "2") (pinfunction "2_2") (pintype "passive"))
      (node (ref "U1") (pin "93") (pinfunction "PG8_93") (pintype "bidirectional"))
    )
    (net (code "183") (name "Net-(U1B-PG9)") (class "Default")
      (node (ref "R64") (pin "2") (pinfunction "2_2") (pintype "passive"))
      (node (ref "U1") (pin "124") (pinfunction "PG9_124") (pintype "bidirectional"))
    )
    (net (code "184") (name "Net-(U1B-PG10)") (class "Default")
      (node (ref "R66") (pin "2") (pinfunction "2_2") (pintype "passive"))
      (node (ref "U1") (pin "125") (pinfunction "PG10_125") (pintype "bidirectional"))
    )
    (net (code "185") (name "Net-(U1B-PG11)") (class "Default")
      (node (ref "R69") (pin "2") (pinfunction "2_2") (pintype "passive"))
      (node (ref "U1") (pin "126") (pinfunction "PG11_126") (pintype "bidirectional"))
    )
    (net (code "186") (name "Net-(U1B-PG12)") (class "Default")
      (node (ref "R71") (pin "2") (pinfunction "2_2") (pintype "passive"))
      (node (ref "U1") (pin "127") (pinfunction "PG12_127") (pintype "bidirectional"))
    )
    (net (code "187") (name "Net-(U1B-PG13)") (class "Default")
      (node (ref "R73") (pin "2") (pinfunction "2_2") (pintype "passive"))
      (node (ref "U1") (pin "128") (pinfunction "PG13_128") (pintype "bidirectional"))
    )
    (net (code "188") (name "Net-(U1B-PG14)") (class "Default")
      (node (ref "R76") (pin "2") (pinfunction "2_2") (pintype "passive"))
      (node (ref "U1") (pin "129") (pinfunction "PG14_129") (pintype "bidirectional"))
    )
    (net (code "189") (name "Net-(U1B-PG15)") (class "Default")
      (node (ref "R78") (pin "2") (pinfunction "2_2") (pintype "passive"))
      (node (ref "U1") (pin "132") (pinfunction "PG15_132") (pintype "bidirectional"))
    )
    (net (code "190") (name "Net-(U2-PFBIN1)") (class "Default")
      (node (ref "C23") (pin "1") (pinfunction "1_1") (pintype "passive"))
      (node (ref "C24") (pin "1") (pinfunction "1_1") (pintype "passive"))
      (node (ref "C25") (pin "1") (pinfunction "1_1") (pintype "passive"))
      (node (ref "C26") (pin "1") (pinfunction "1_1") (pintype "passive"))
      (node (ref "U2") (pin "18") (pinfunction "PFBIN1_18") (pintype "input"))
      (node (ref "U2") (pin "23") (pinfunction "PFBOUT_23") (pintype "output"))
      (node (ref "U2") (pin "37") (pinfunction "PFBIN2_37") (pintype "input"))
    )
    (net (code "191") (name "Net-(U2-PWR_DOWN{slash}INT)") (class "Default")
      (node (ref "R81") (pin "1") (pinfunction "1_1") (pintype "passive"))
      (node (ref "U2") (pin "7") (pinfunction "PWR_DOWN/INT_7") (pintype "input"))
    )
    (net (code "192") (name "Net-(U2-RBIAS)") (class "Default")
      (node (ref "R84") (pin "1") (pinfunction "1_1") (pintype "passive"))
      (node (ref "U2") (pin "24") (pinfunction "RBIAS_24") (pintype "input"))
    )
    (net (code "193") (name "Net-(U2-RESERVED_32)") (class "Default")
      (node (ref "R82") (pin "1") (pinfunction "1_1") (pintype "passive"))
      (node (ref "U2") (pin "21") (pinfunction "RESERVED_32_21") (pintype "bidirectional"))
    )
    (net (code "194") (name "Net-(U2-RESERVED_48)") (class "Default")
      (node (ref "R83") (pin "1") (pinfunction "1_1") (pintype "passive"))
      (node (ref "U2") (pin "20") (pinfunction "RESERVED_48_20") (pintype "bidirectional"))
    )
    (net (code "195") (name "Net-(U3-IN)") (class "Default")
      (node (ref "C34") (pin "1") (pinfunction "1_1") (pintype "passive"))
      (node (ref "F1") (pin "2") (pinfunction "2_2") (pintype "passive"))
      (node (ref "U3") (pin "3") (pinfunction "IN_3") (pintype "power_in"))
    )
    (net (code "196") (name "Net-(U4-OUT)") (class "Default")
      (node (ref "R102") (pin "2") (pinfunction "2_2") (pintype "passive"))
      (node (ref "R105") (pin "1") (pinfunction "1_1") (pintype "passive"))
      (node (ref "U4") (pin "3") (pinfunction "OUT_3") (pintype "power_in"))
    )
    (net (code "197") (name "Net-(U4-SW)") (class "Default")
      (node (ref "R99") (pin "1") (pinfunction "1_1") (pintype "passive"))
      (node (ref "U4") (pin "1") (pinfunction "SW_1") (pintype "passive"))
    )
    (net (code "198") (name "VCC") (class "Default")
      (node (ref "C10") (pin "1") (pinfunction "+_1") (pintype "passive"))
      (node (ref "C13") (pin "1") (pinfunction "+_1") (pintype "passive"))
      (node (ref "C14") (pin "1") (pinfunction "+_1") (pintype "passive"))
      (node (ref "C15") (pin "1") (pinfunction "+_1") (pintype "passive"))
      (node (ref "C16") (pin "1") (pinfunction "+_1") (pintype "passive"))
      (node (ref "C17") (pin "1") (pinfunction "1_1") (pintype "passive"))
      (node (ref "C18") (pin "1") (pinfunction "+_1") (pintype "passive"))
      (node (ref "C19") (pin "1") (pinfunction "+_1") (pintype "passive"))
      (node (ref "C20") (pin "1") (pinfunction "+_1") (pintype "passive"))
      (node (ref "C21") (pin "1") (pinfunction "+_1") (pintype "passive"))
      (node (ref "C27") (pin "1") (pinfunction "1_1") (pintype "passive"))
      (node (ref "C28") (pin "1") (pinfunction "1_1") (pintype "passive"))
      (node (ref "C29") (pin "1") (pinfunction "1_1") (pintype "passive"))
      (node (ref "C30") (pin "1") (pinfunction "1_1") (pintype "passive"))
      (node (ref "C31") (pin "1") (pinfunction "1_1") (pintype "passive"))
      (node (ref "C32") (pin "1") (pinfunction "1_1") (pintype "passive"))
      (node (ref "C33") (pin "1") (pinfunction "1_1") (pintype "passive"))
      (node (ref "C35") (pin "1") (pinfunction "1_1") (pintype "passive"))
      (node (ref "C5") (pin "1") (pinfunction "1_1") (pintype "passive"))
      (node (ref "C6") (pin "1") (pinfunction "+_1") (pintype "passive"))
      (node (ref "C7") (pin "1") (pinfunction "+_1") (pintype "passive"))
      (node (ref "C8") (pin "1") (pinfunction "+_1") (pintype "passive"))
      (node (ref "C9") (pin "1") (pinfunction "+_1") (pintype "passive"))
      (node (ref "D5") (pin "1") (pinfunction "A_1") (pintype "passive"))
      (node (ref "J1") (pin "4") (pinfunction "VDD_4") (pintype "passive"))
      (node (ref "P1") (pin "1") (pinfunction "1_1") (pintype "passive"))
      (node (ref "P1") (pin "20") (pinfunction "20_20") (pintype "passive"))
      (node (ref "P2") (pin "1") (pinfunction "1_1") (pintype "passive"))
      (node (ref "P2") (pin "2") (pinfunction "2_2") (pintype "passive"))
      (node (ref "P3") (pin "1") (pinfunction "1_1") (pintype "passive"))
      (node (ref "P3") (pin "2") (pinfunction "2_2") (pintype "passive"))
      (node (ref "P4") (pin "1") (pinfunction "1_1") (pintype "passive"))
      (node (ref "P4") (pin "2") (pinfunction "2_2") (pintype "passive"))
      (node (ref "P6") (pin "4") (pinfunction "4_4") (pintype "passive"))
      (node (ref "P8") (pin "12") (pinfunction "YLW+_12") (pintype "passive"))
      (node (ref "P8") (pin "4") (pinfunction "TCT_4") (pintype "passive"))
      (node (ref "P8") (pin "5") (pinfunction "RCT_5") (pintype "passive"))
      (node (ref "P8") (pin "9") (pinfunction "GRN+_9") (pintype "passive"))
      (node (ref "R100") (pin "2") (pinfunction "2_2") (pintype "passive"))
      (node (ref "R101") (pin "2") (pinfunction "2_2") (pintype "passive"))
      (node (ref "R103") (pin "2") (pinfunction "2_2") (pintype "passive"))
      (node (ref "R106") (pin "2") (pinfunction "2_2") (pintype "passive"))
      (node (ref "R107") (pin "2") (pinfunction "2_2") (pintype "passive"))
      (node (ref "R80") (pin "2") (pinfunction "2_2") (pintype "passive"))
      (node (ref "R81") (pin "2") (pinfunction "2_2") (pintype "passive"))
      (node (ref "R82") (pin "2") (pinfunction "2_2") (pintype "passive"))
      (node (ref "R83") (pin "2") (pinfunction "2_2") (pintype "passive"))
      (node (ref "R85") (pin "2") (pinfunction "2_2") (pintype "passive"))
      (node (ref "R87") (pin "2") (pinfunction "2_2") (pintype "passive"))
      (node (ref "R88") (pin "2") (pinfunction "2_2") (pintype "passive"))
      (node (ref "R95") (pin "2") (pinfunction "2_2") (pintype "passive"))
      (node (ref "R96") (pin "1") (pinfunction "1_1") (pintype "passive"))
      (node (ref "R97") (pin "2") (pinfunction "2_2") (pintype "passive"))
      (node (ref "R98") (pin "2") (pinfunction "2_2") (pintype "passive"))
      (node (ref "R99") (pin "2") (pinfunction "2_2") (pintype "passive"))
      (node (ref "U1") (pin "108") (pinfunction "VDD_108") (pintype "power_in"))
      (node (ref "U1") (pin "121") (pinfunction "VDD_121") (pintype "power_in"))
      (node (ref "U1") (pin "131") (pinfunction "VDD_131") (pintype "power_in"))
      (node (ref "U1") (pin "143") (pinfunction "PDR_ON_143") (pintype "input"))
      (node (ref "U1") (pin "144") (pinfunction "VDD_144") (pintype "power_in"))
      (node (ref "U1") (pin "17") (pinfunction "VDD_17") (pintype "power_in"))
      (node (ref "U1") (pin "30") (pinfunction "VDD_30") (pintype "power_in"))
      (node (ref "U1") (pin "32") (pinfunction "VREF+_32") (pintype "power_in"))
      (node (ref "U1") (pin "33") (pinfunction "VDDA_33") (pintype "power_in"))
      (node (ref "U1") (pin "39") (pinfunction "VDD_39") (pintype "power_in"))
      (node (ref "U1") (pin "52") (pinfunction "VDD_52") (pintype "power_in"))
      (node (ref "U1") (pin "6") (pinfunction "VBAT_6") (pintype "power_in"))
      (node (ref "U1") (pin "62") (pinfunction "VDD_62") (pintype "power_in"))
      (node (ref "U1") (pin "72") (pinfunction "VDD_72") (pintype "power_in"))
      (node (ref "U1") (pin "84") (pinfunction "VDD_84") (pintype "power_in"))
      (node (ref "U1") (pin "95") (pinfunction "VDD_95") (pintype "power_in"))
      (node (ref "U2") (pin "22") (pinfunction "AVDD33_22") (pintype "power_in"))
      (node (ref "U2") (pin "32") (pinfunction "IOVDD33_32_32") (pintype "power_in"))
      (node (ref "U2") (pin "48") (pinfunction "IOVDD33_48_48") (pintype "power_in"))
      (node (ref "U4") (pin "4") (pinfunction "VDD_4") (pintype "power_in"))
    )
    (net (code "199") (name "unconnected-(J1-CD-Pad9)") (class "Default")
      (node (ref "J1") (pin "9") (pinfunction "CD_9") (pintype "passive+no_connect"))
    )
    (net (code "200") (name "unconnected-(J1-DAT1-Pad8)") (class "Default")
      (node (ref "J1") (pin "8") (pinfunction "DAT1_8") (pintype "passive+no_connect"))
    )
    (net (code "201") (name "unconnected-(J1-DAT2-Pad1)") (class "Default")
      (node (ref "J1") (pin "1") (pinfunction "DAT2_1") (pintype "passive+no_connect"))
    )
    (net (code "202") (name "unconnected-(P8-NC-Pad7)") (class "Default")
      (node (ref "P8") (pin "7") (pinfunction "NC_7") (pintype "passive+no_connect"))
    )
    (net (code "203") (name "unconnected-(U1A-PA0-WKUP(PA0)-Pad34)") (class "Default")
      (node (ref "U1") (pin "34") (pinfunction "PA0-WKUP(PA0)_34") (pintype "bidirectional+no_connect"))
    )
    (net (code "204") (name "unconnected-(U1A-PA3-Pad37)") (class "Default")
      (node (ref "U1") (pin "37") (pinfunction "PA3_37") (pintype "bidirectional+no_connect"))
    )
    (net (code "205") (name "unconnected-(U1A-PA6-Pad42)") (class "Default")
      (node (ref "U1") (pin "42") (pinfunction "PA6_42") (pintype "bidirectional+no_connect"))
    )
    (net (code "206") (name "unconnected-(U1A-PA11-Pad103)") (class "Default")
      (node (ref "U1") (pin "103") (pinfunction "PA11_103") (pintype "bidirectional+no_connect"))
    )
    (net (code "207") (name "unconnected-(U1A-PA12-Pad104)") (class "Default")
      (node (ref "U1") (pin "104") (pinfunction "PA12_104") (pintype "bidirectional+no_connect"))
    )
    (net (code "208") (name "unconnected-(U1A-PA15(JTDI)-Pad110)") (class "Default")
      (node (ref "U1") (pin "110") (pinfunction "PA15(JTDI)_110") (pintype "bidirectional+no_connect"))
    )
    (net (code "209") (name "unconnected-(U1A-PB6-Pad136)") (class "Default")
      (node (ref "U1") (pin "136") (pinfunction "PB6_136") (pintype "bidirectional+no_connect"))
    )
    (net (code "210") (name "unconnected-(U1A-PB7-Pad137)") (class "Default")
      (node (ref "U1") (pin "137") (pinfunction "PB7_137") (pintype "bidirectional+no_connect"))
    )
    (net (code "211") (name "unconnected-(U1A-PB10-Pad69)") (class "Default")
      (node (ref "U1") (pin "69") (pinfunction "PB10_69") (pintype "bidirectional+no_connect"))
    )
    (net (code "212") (name "unconnected-(U1A-PB14-Pad75)") (class "Default")
      (node (ref "U1") (pin "75") (pinfunction "PB14_75") (pintype "bidirectional+no_connect"))
    )
    (net (code "213") (name "unconnected-(U1A-PB15-Pad76)") (class "Default")
      (node (ref "U1") (pin "76") (pinfunction "PB15_76") (pintype "bidirectional"))
    )
    (net (code "214") (name "unconnected-(U1A-PC0-Pad26)") (class "Default")
      (node (ref "U1") (pin "26") (pinfunction "PC0_26") (pintype "bidirectional+no_connect"))
    )
    (net (code "215") (name "unconnected-(U1A-PC2-Pad28)") (class "Default")
      (node (ref "U1") (pin "28") (pinfunction "PC2_28") (pintype "bidirectional+no_connect"))
    )
    (net (code "216") (name "unconnected-(U1A-PC3-Pad29)") (class "Default")
      (node (ref "U1") (pin "29") (pinfunction "PC3_29") (pintype "bidirectional+no_connect"))
    )
    (net (code "217") (name "unconnected-(U1A-PC6-Pad96)") (class "Default")
      (node (ref "U1") (pin "96") (pinfunction "PC6_96") (pintype "bidirectional+no_connect"))
    )
    (net (code "218") (name "unconnected-(U1A-PC7-Pad97)") (class "Default")
      (node (ref "U1") (pin "97") (pinfunction "PC7_97") (pintype "bidirectional+no_connect"))
    )
    (net (code "219") (name "unconnected-(U1A-PC8-Pad98)") (class "Default")
      (node (ref "U1") (pin "98") (pinfunction "PC8_98") (pintype "bidirectional+no_connect"))
    )
    (net (code "220") (name "unconnected-(U1A-PC9-Pad99)") (class "Default")
      (node (ref "U1") (pin "99") (pinfunction "PC9_99") (pintype "bidirectional+no_connect"))
    )
    (net (code "221") (name "unconnected-(U1A-PC10-Pad111)") (class "Default")
      (node (ref "U1") (pin "111") (pinfunction "PC10_111") (pintype "bidirectional+no_connect"))
    )
    (net (code "222") (name "unconnected-(U1A-PC13-Pad7)") (class "Default")
      (node (ref "U1") (pin "7") (pinfunction "PC13_7") (pintype "bidirectional+no_connect"))
    )
    (net (code "223") (name "unconnected-(U1A-PC14-OSC32_IN(PC14)-Pad8)") (class "Default")
      (node (ref "U1") (pin "8") (pinfunction "PC14-OSC32_IN(PC14)_8") (pintype "bidirectional+no_connect"))
    )
    (net (code "224") (name "unconnected-(U1A-PC15-OSC32_OUT(PC15)-Pad9)") (class "Default")
      (node (ref "U1") (pin "9") (pinfunction "PC15-OSC32_OUT(PC15)_9") (pintype "bidirectional+no_connect"))
    )
    (net (code "225") (name "unconnected-(U1B-PE11-Pad64)") (class "Default")
      (node (ref "U1") (pin "64") (pinfunction "PE11_64") (pintype "bidirectional+no_connect"))
    )
    (net (code "226") (name "unconnected-(U2-COL{slash}PHYAD0-Pad42)") (class "Default")
      (node (ref "U2") (pin "42") (pinfunction "COL/PHYAD0_42") (pintype "output+no_connect"))
    )
    (net (code "227") (name "unconnected-(U2-RXD_2{slash}PHYAD3-Pad45)") (class "Default")
      (node (ref "U2") (pin "45") (pinfunction "RXD_2/PHYAD3_45") (pintype "output+no_connect"))
    )
    (net (code "228") (name "unconnected-(U2-RXD_3{slash}PHYAD4-Pad46)") (class "Default")
      (node (ref "U2") (pin "46") (pinfunction "RXD_3/PHYAD4_46") (pintype "output+no_connect"))
    )
    (net (code "229") (name "unconnected-(U2-RX_CLK-Pad38)") (class "Default")
      (node (ref "U2") (pin "38") (pinfunction "RX_CLK_38") (pintype "output+no_connect"))
    )
    (net (code "230") (name "unconnected-(U2-RX_ER{slash}MDIX_EN-Pad41)") (class "Default")
      (node (ref "U2") (pin "41") (pinfunction "RX_ER/MDIX_EN_41") (pintype "output+no_connect"))
    )
    (net (code "231") (name "unconnected-(U2-TCK-Pad8)") (class "Default")
      (node (ref "U2") (pin "8") (pinfunction "TCK_8") (pintype "input+no_connect"))
    )
    (net (code "232") (name "unconnected-(U2-TDI-Pad12)") (class "Default")
      (node (ref "U2") (pin "12") (pinfunction "TDI_12") (pintype "input+no_connect"))
    )
    (net (code "233") (name "unconnected-(U2-TDO-Pad9)") (class "Default")
      (node (ref "U2") (pin "9") (pinfunction "TDO_9") (pintype "output+no_connect"))
    )
    (net (code "234") (name "unconnected-(U2-TMS-Pad10)") (class "Default")
      (node (ref "U2") (pin "10") (pinfunction "TMS_10") (pintype "input+no_connect"))
    )
    (net (code "235") (name "unconnected-(U2-TXD_2-Pad5)") (class "Default")
      (node (ref "U2") (pin "5") (pinfunction "TXD_2_5") (pintype "input+no_connect"))
    )
    (net (code "236") (name "unconnected-(U2-TX_CLK-Pad1)") (class "Default")
      (node (ref "U2") (pin "1") (pinfunction "TX_CLK_1") (pintype "output"))
    )
    (net (code "237") (name "unconnected-(U2-X2-Pad33)") (class "Default")
      (node (ref "U2") (pin "33") (pinfunction "X2_33") (pintype "output+no_connect"))
    )
    (net (code "238") (name "unconnected-(U2-~{TRST}-Pad11)") (class "Default")
      (node (ref "U2") (pin "11") (pinfunction "~{TRST}_11") (pintype "input+no_connect"))
    )
  )
)
